# SCH_LED-bargraph-1_5_2024-10-24.net
KiCad netlist of a schematic drawn in EasyEDA
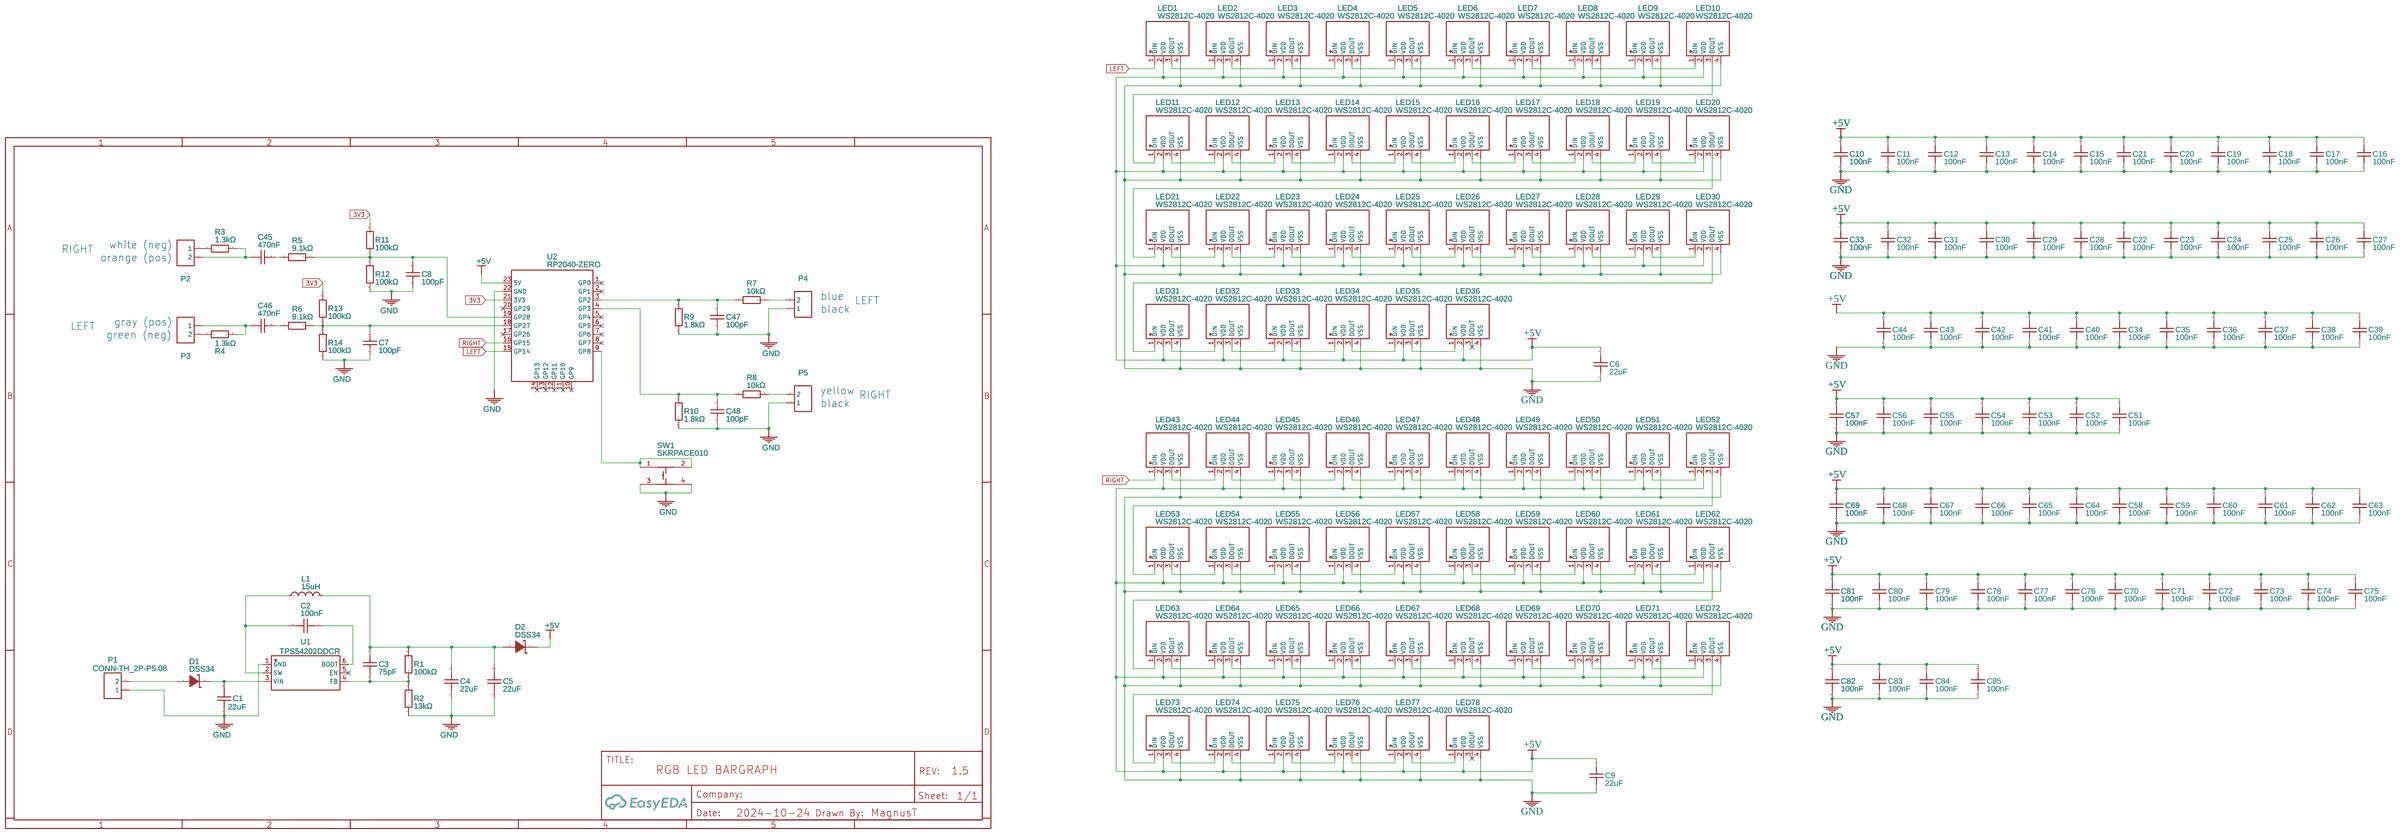
[diagram p0: schematic sheet]

(export (version "E")
  (design (tool "Eeschema 10.0.6"))
  (components
    (comp (ref "C1")
      (value "22uF")
      (fields
        (field (name "Manufacturer Part") "CL21A226MAYNNNE")
        (field (name "Manufacturer") "Samsung Electro-Mechanics")
      )
      (libsource (lib "") (part "CL21A226MAYNNNE"))
    )
    (comp (ref "C2")
      (value "100nF")
      (fields
        (field (name "Manufacturer Part") "CL05B104KO5NNNC")
        (field (name "Manufacturer") "SAMSUNG(三星)")
      )
      (libsource (lib "") (part "CL05B104KO5NNNC_1"))
    )
    (comp (ref "C3")
      (value "75pF")
      (fields
        (field (name "Manufacturer Part") "CC0603JRNPO9BN750")
        (field (name "Manufacturer") "YAGEO(国巨)")
      )
      (libsource (lib "") (part "CC0603JRNPO9BN750"))
    )
    (comp (ref "C4")
      (value "22uF")
      (fields (field (name "Manufacturer Part") "CL10A226MQ8NRNC") (field (name "Manufacturer") "SAMSUNG"))
      (libsource (lib "") (part "CL10A226MQ8NRNC"))
    )
    (comp (ref "C5")
      (value "22uF")
      (fields (field (name "Manufacturer Part") "CL10A226MQ8NRNC") (field (name "Manufacturer") "SAMSUNG"))
      (libsource (lib "") (part "CL10A226MQ8NRNC"))
    )
    (comp (ref "C6")
      (value "22uF")
      (fields (field (name "Manufacturer Part") "CL10A226MQ8NRNC") (field (name "Manufacturer") "SAMSUNG"))
      (libsource (lib "") (part "CL10A226MQ8NRNC"))
    )
    (comp (ref "C7")
      (value "100pF")
      (fields
        (field (name "Manufacturer Part") "CL10C101JB8NNNC")
        (field (name "Manufacturer") "SAMSUNG(三星)")
      )
      (libsource (lib "") (part "CL10C101JB8NNNC"))
    )
    (comp (ref "C8")
      (value "100pF")
      (fields
        (field (name "Manufacturer Part") "CL10C101JB8NNNC")
        (field (name "Manufacturer") "SAMSUNG(三星)")
      )
      (libsource (lib "") (part "CL10C101JB8NNNC"))
    )
    (comp (ref "C9")
      (value "22uF")
      (fields (field (name "Manufacturer Part") "CL10A226MQ8NRNC") (field (name "Manufacturer") "SAMSUNG"))
      (libsource (lib "") (part "CL10A226MQ8NRNC"))
    )
    (comp (ref "C10")
      (value "100nF")
      (fields
        (field (name "Manufacturer Part") "CL05B104KO5NNNC")
        (field (name "Manufacturer") "SAMSUNG(三星)")
      )
      (libsource (lib "") (part "CL05B104KO5NNNC"))
    )
    (comp (ref "C11")
      (value "100nF")
      (fields
        (field (name "Manufacturer Part") "CL05B104KO5NNNC")
        (field (name "Manufacturer") "SAMSUNG(三星)")
      )
      (libsource (lib "") (part "CL05B104KO5NNNC"))
    )
    (comp (ref "C12")
      (value "100nF")
      (fields
        (field (name "Manufacturer Part") "CL05B104KO5NNNC")
        (field (name "Manufacturer") "SAMSUNG(三星)")
      )
      (libsource (lib "") (part "CL05B104KO5NNNC"))
    )
    (comp (ref "C13")
      (value "100nF")
      (fields
        (field (name "Manufacturer Part") "CL05B104KO5NNNC")
        (field (name "Manufacturer") "SAMSUNG(三星)")
      )
      (libsource (lib "") (part "CL05B104KO5NNNC"))
    )
    (comp (ref "C14")
      (value "100nF")
      (fields
        (field (name "Manufacturer Part") "CL05B104KO5NNNC")
        (field (name "Manufacturer") "SAMSUNG(三星)")
      )
      (libsource (lib "") (part "CL05B104KO5NNNC"))
    )
    (comp (ref "C15")
      (value "100nF")
      (fields
        (field (name "Manufacturer Part") "CL05B104KO5NNNC")
        (field (name "Manufacturer") "SAMSUNG(三星)")
      )
      (libsource (lib "") (part "CL05B104KO5NNNC"))
    )
    (comp (ref "C16")
      (value "100nF")
      (fields
        (field (name "Manufacturer Part") "CL05B104KO5NNNC")
        (field (name "Manufacturer") "SAMSUNG(三星)")
      )
      (libsource (lib "") (part "CL05B104KO5NNNC"))
    )
    (comp (ref "C17")
      (value "100nF")
      (fields
        (field (name "Manufacturer Part") "CL05B104KO5NNNC")
        (field (name "Manufacturer") "SAMSUNG(三星)")
      )
      (libsource (lib "") (part "CL05B104KO5NNNC"))
    )
    (comp (ref "C18")
      (value "100nF")
      (fields
        (field (name "Manufacturer Part") "CL05B104KO5NNNC")
        (field (name "Manufacturer") "SAMSUNG(三星)")
      )
      (libsource (lib "") (part "CL05B104KO5NNNC"))
    )
    (comp (ref "C19")
      (value "100nF")
      (fields
        (field (name "Manufacturer Part") "CL05B104KO5NNNC")
        (field (name "Manufacturer") "SAMSUNG(三星)")
      )
      (libsource (lib "") (part "CL05B104KO5NNNC"))
    )
    (comp (ref "C20")
      (value "100nF")
      (fields
        (field (name "Manufacturer Part") "CL05B104KO5NNNC")
        (field (name "Manufacturer") "SAMSUNG(三星)")
      )
      (libsource (lib "") (part "CL05B104KO5NNNC"))
    )
    (comp (ref "C21")
      (value "100nF")
      (fields
        (field (name "Manufacturer Part") "CL05B104KO5NNNC")
        (field (name "Manufacturer") "SAMSUNG(三星)")
      )
      (libsource (lib "") (part "CL05B104KO5NNNC"))
    )
    (comp (ref "C22")
      (value "100nF")
      (fields
        (field (name "Manufacturer Part") "CL05B104KO5NNNC")
        (field (name "Manufacturer") "SAMSUNG(三星)")
      )
      (libsource (lib "") (part "CL05B104KO5NNNC"))
    )
    (comp (ref "C23")
      (value "100nF")
      (fields
        (field (name "Manufacturer Part") "CL05B104KO5NNNC")
        (field (name "Manufacturer") "SAMSUNG(三星)")
      )
      (libsource (lib "") (part "CL05B104KO5NNNC"))
    )
    (comp (ref "C24")
      (value "100nF")
      (fields
        (field (name "Manufacturer Part") "CL05B104KO5NNNC")
        (field (name "Manufacturer") "SAMSUNG(三星)")
      )
      (libsource (lib "") (part "CL05B104KO5NNNC"))
    )
    (comp (ref "C25")
      (value "100nF")
      (fields
        (field (name "Manufacturer Part") "CL05B104KO5NNNC")
        (field (name "Manufacturer") "SAMSUNG(三星)")
      )
      (libsource (lib "") (part "CL05B104KO5NNNC"))
    )
    (comp (ref "C26")
      (value "100nF")
      (fields
        (field (name "Manufacturer Part") "CL05B104KO5NNNC")
        (field (name "Manufacturer") "SAMSUNG(三星)")
      )
      (libsource (lib "") (part "CL05B104KO5NNNC"))
    )
    (comp (ref "C27")
      (value "100nF")
      (fields
        (field (name "Manufacturer Part") "CL05B104KO5NNNC")
        (field (name "Manufacturer") "SAMSUNG(三星)")
      )
      (libsource (lib "") (part "CL05B104KO5NNNC"))
    )
    (comp (ref "C28")
      (value "100nF")
      (fields
        (field (name "Manufacturer Part") "CL05B104KO5NNNC")
        (field (name "Manufacturer") "SAMSUNG(三星)")
      )
      (libsource (lib "") (part "CL05B104KO5NNNC"))
    )
    (comp (ref "C29")
      (value "100nF")
      (fields
        (field (name "Manufacturer Part") "CL05B104KO5NNNC")
        (field (name "Manufacturer") "SAMSUNG(三星)")
      )
      (libsource (lib "") (part "CL05B104KO5NNNC"))
    )
    (comp (ref "C30")
      (value "100nF")
      (fields
        (field (name "Manufacturer Part") "CL05B104KO5NNNC")
        (field (name "Manufacturer") "SAMSUNG(三星)")
      )
      (libsource (lib "") (part "CL05B104KO5NNNC"))
    )
    (comp (ref "C31")
      (value "100nF")
      (fields
        (field (name "Manufacturer Part") "CL05B104KO5NNNC")
        (field (name "Manufacturer") "SAMSUNG(三星)")
      )
      (libsource (lib "") (part "CL05B104KO5NNNC"))
    )
    (comp (ref "C32")
      (value "100nF")
      (fields
        (field (name "Manufacturer Part") "CL05B104KO5NNNC")
        (field (name "Manufacturer") "SAMSUNG(三星)")
      )
      (libsource (lib "") (part "CL05B104KO5NNNC"))
    )
    (comp (ref "C33")
      (value "100nF")
      (fields
        (field (name "Manufacturer Part") "CL05B104KO5NNNC")
        (field (name "Manufacturer") "SAMSUNG(三星)")
      )
      (libsource (lib "") (part "CL05B104KO5NNNC"))
    )
    (comp (ref "C34")
      (value "100nF")
      (fields
        (field (name "Manufacturer Part") "CL05B104KO5NNNC")
        (field (name "Manufacturer") "SAMSUNG(三星)")
      )
      (libsource (lib "") (part "CL05B104KO5NNNC"))
    )
    (comp (ref "C35")
      (value "100nF")
      (fields
        (field (name "Manufacturer Part") "CL05B104KO5NNNC")
        (field (name "Manufacturer") "SAMSUNG(三星)")
      )
      (libsource (lib "") (part "CL05B104KO5NNNC"))
    )
    (comp (ref "C36")
      (value "100nF")
      (fields
        (field (name "Manufacturer Part") "CL05B104KO5NNNC")
        (field (name "Manufacturer") "SAMSUNG(三星)")
      )
      (libsource (lib "") (part "CL05B104KO5NNNC"))
    )
    (comp (ref "C37")
      (value "100nF")
      (fields
        (field (name "Manufacturer Part") "CL05B104KO5NNNC")
        (field (name "Manufacturer") "SAMSUNG(三星)")
      )
      (libsource (lib "") (part "CL05B104KO5NNNC"))
    )
    (comp (ref "C38")
      (value "100nF")
      (fields
        (field (name "Manufacturer Part") "CL05B104KO5NNNC")
        (field (name "Manufacturer") "SAMSUNG(三星)")
      )
      (libsource (lib "") (part "CL05B104KO5NNNC"))
    )
    (comp (ref "C39")
      (value "100nF")
      (fields
        (field (name "Manufacturer Part") "CL05B104KO5NNNC")
        (field (name "Manufacturer") "SAMSUNG(三星)")
      )
      (libsource (lib "") (part "CL05B104KO5NNNC"))
    )
    (comp (ref "C40")
      (value "100nF")
      (fields
        (field (name "Manufacturer Part") "CL05B104KO5NNNC")
        (field (name "Manufacturer") "SAMSUNG(三星)")
      )
      (libsource (lib "") (part "CL05B104KO5NNNC"))
    )
    (comp (ref "C41")
      (value "100nF")
      (fields
        (field (name "Manufacturer Part") "CL05B104KO5NNNC")
        (field (name "Manufacturer") "SAMSUNG(三星)")
      )
      (libsource (lib "") (part "CL05B104KO5NNNC"))
    )
    (comp (ref "C42")
      (value "100nF")
      (fields
        (field (name "Manufacturer Part") "CL05B104KO5NNNC")
        (field (name "Manufacturer") "SAMSUNG(三星)")
      )
      (libsource (lib "") (part "CL05B104KO5NNNC"))
    )
    (comp (ref "C43")
      (value "100nF")
      (fields
        (field (name "Manufacturer Part") "CL05B104KO5NNNC")
        (field (name "Manufacturer") "SAMSUNG(三星)")
      )
      (libsource (lib "") (part "CL05B104KO5NNNC"))
    )
    (comp (ref "C44")
      (value "100nF")
      (fields
        (field (name "Manufacturer Part") "CL05B104KO5NNNC")
        (field (name "Manufacturer") "SAMSUNG(三星)")
      )
      (libsource (lib "") (part "CL05B104KO5NNNC"))
    )
    (comp (ref "C45")
      (value "470nF")
      (fields
        (field (name "Manufacturer Part") "CL21B474KBFNNNE")
        (field (name "Manufacturer") "SAMSUNG(三星)")
      )
      (libsource (lib "") (part "CL21B474KBFNNNE"))
    )
    (comp (ref "C46")
      (value "470nF")
      (fields
        (field (name "Manufacturer Part") "CL21B474KBFNNNE")
        (field (name "Manufacturer") "SAMSUNG(三星)")
      )
      (libsource (lib "") (part "CL21B474KBFNNNE"))
    )
    (comp (ref "C47")
      (value "100pF")
      (fields
        (field (name "Manufacturer Part") "CL10C101JB8NNNC")
        (field (name "Manufacturer") "SAMSUNG(三星)")
      )
      (libsource (lib "") (part "CL10C101JB8NNNC"))
    )
    (comp (ref "C48")
      (value "100pF")
      (fields
        (field (name "Manufacturer Part") "CL10C101JB8NNNC")
        (field (name "Manufacturer") "SAMSUNG(三星)")
      )
      (libsource (lib "") (part "CL10C101JB8NNNC"))
    )
    (comp (ref "C51")
      (value "100nF")
      (fields
        (field (name "Manufacturer Part") "CL05B104KO5NNNC")
        (field (name "Manufacturer") "SAMSUNG(三星)")
      )
      (libsource (lib "") (part "CL05B104KO5NNNC"))
    )
    (comp (ref "C52")
      (value "100nF")
      (fields
        (field (name "Manufacturer Part") "CL05B104KO5NNNC")
        (field (name "Manufacturer") "SAMSUNG(三星)")
      )
      (libsource (lib "") (part "CL05B104KO5NNNC"))
    )
    (comp (ref "C53")
      (value "100nF")
      (fields
        (field (name "Manufacturer Part") "CL05B104KO5NNNC")
        (field (name "Manufacturer") "SAMSUNG(三星)")
      )
      (libsource (lib "") (part "CL05B104KO5NNNC"))
    )
    (comp (ref "C54")
      (value "100nF")
      (fields
        (field (name "Manufacturer Part") "CL05B104KO5NNNC")
        (field (name "Manufacturer") "SAMSUNG(三星)")
      )
      (libsource (lib "") (part "CL05B104KO5NNNC"))
    )
    (comp (ref "C55")
      (value "100nF")
      (fields
        (field (name "Manufacturer Part") "CL05B104KO5NNNC")
        (field (name "Manufacturer") "SAMSUNG(三星)")
      )
      (libsource (lib "") (part "CL05B104KO5NNNC"))
    )
    (comp (ref "C56")
      (value "100nF")
      (fields
        (field (name "Manufacturer Part") "CL05B104KO5NNNC")
        (field (name "Manufacturer") "SAMSUNG(三星)")
      )
      (libsource (lib "") (part "CL05B104KO5NNNC"))
    )
    (comp (ref "C57")
      (value "100nF")
      (fields
        (field (name "Manufacturer Part") "CL05B104KO5NNNC")
        (field (name "Manufacturer") "SAMSUNG(三星)")
      )
      (libsource (lib "") (part "CL05B104KO5NNNC"))
    )
    (comp (ref "C58")
      (value "100nF")
      (fields
        (field (name "Manufacturer Part") "CL05B104KO5NNNC")
        (field (name "Manufacturer") "SAMSUNG(三星)")
      )
      (libsource (lib "") (part "CL05B104KO5NNNC"))
    )
    (comp (ref "C59")
      (value "100nF")
      (fields
        (field (name "Manufacturer Part") "CL05B104KO5NNNC")
        (field (name "Manufacturer") "SAMSUNG(三星)")
      )
      (libsource (lib "") (part "CL05B104KO5NNNC"))
    )
    (comp (ref "C60")
      (value "100nF")
      (fields
        (field (name "Manufacturer Part") "CL05B104KO5NNNC")
        (field (name "Manufacturer") "SAMSUNG(三星)")
      )
      (libsource (lib "") (part "CL05B104KO5NNNC"))
    )
    (comp (ref "C61")
      (value "100nF")
      (fields
        (field (name "Manufacturer Part") "CL05B104KO5NNNC")
        (field (name "Manufacturer") "SAMSUNG(三星)")
      )
      (libsource (lib "") (part "CL05B104KO5NNNC"))
    )
    (comp (ref "C62")
      (value "100nF")
      (fields
        (field (name "Manufacturer Part") "CL05B104KO5NNNC")
        (field (name "Manufacturer") "SAMSUNG(三星)")
      )
      (libsource (lib "") (part "CL05B104KO5NNNC"))
    )
    (comp (ref "C63")
      (value "100nF")
      (fields
        (field (name "Manufacturer Part") "CL05B104KO5NNNC")
        (field (name "Manufacturer") "SAMSUNG(三星)")
      )
      (libsource (lib "") (part "CL05B104KO5NNNC"))
    )
    (comp (ref "C64")
      (value "100nF")
      (fields
        (field (name "Manufacturer Part") "CL05B104KO5NNNC")
        (field (name "Manufacturer") "SAMSUNG(三星)")
      )
      (libsource (lib "") (part "CL05B104KO5NNNC"))
    )
    (comp (ref "C65")
      (value "100nF")
      (fields
        (field (name "Manufacturer Part") "CL05B104KO5NNNC")
        (field (name "Manufacturer") "SAMSUNG(三星)")
      )
      (libsource (lib "") (part "CL05B104KO5NNNC"))
    )
    (comp (ref "C66")
      (value "100nF")
      (fields
        (field (name "Manufacturer Part") "CL05B104KO5NNNC")
        (field (name "Manufacturer") "SAMSUNG(三星)")
      )
      (libsource (lib "") (part "CL05B104KO5NNNC"))
    )
    (comp (ref "C67")
      (value "100nF")
      (fields
        (field (name "Manufacturer Part") "CL05B104KO5NNNC")
        (field (name "Manufacturer") "SAMSUNG(三星)")
      )
      (libsource (lib "") (part "CL05B104KO5NNNC"))
    )
    (comp (ref "C68")
      (value "100nF")
      (fields
        (field (name "Manufacturer Part") "CL05B104KO5NNNC")
        (field (name "Manufacturer") "SAMSUNG(三星)")
      )
      (libsource (lib "") (part "CL05B104KO5NNNC"))
    )
    (comp (ref "C69")
      (value "100nF")
      (fields
        (field (name "Manufacturer Part") "CL05B104KO5NNNC")
        (field (name "Manufacturer") "SAMSUNG(三星)")
      )
      (libsource (lib "") (part "CL05B104KO5NNNC"))
    )
    (comp (ref "C70")
      (value "100nF")
      (fields
        (field (name "Manufacturer Part") "CL05B104KO5NNNC")
        (field (name "Manufacturer") "SAMSUNG(三星)")
      )
      (libsource (lib "") (part "CL05B104KO5NNNC"))
    )
    (comp (ref "C71")
      (value "100nF")
      (fields
        (field (name "Manufacturer Part") "CL05B104KO5NNNC")
        (field (name "Manufacturer") "SAMSUNG(三星)")
      )
      (libsource (lib "") (part "CL05B104KO5NNNC"))
    )
    (comp (ref "C72")
      (value "100nF")
      (fields
        (field (name "Manufacturer Part") "CL05B104KO5NNNC")
        (field (name "Manufacturer") "SAMSUNG(三星)")
      )
      (libsource (lib "") (part "CL05B104KO5NNNC"))
    )
    (comp (ref "C73")
      (value "100nF")
      (fields
        (field (name "Manufacturer Part") "CL05B104KO5NNNC")
        (field (name "Manufacturer") "SAMSUNG(三星)")
      )
      (libsource (lib "") (part "CL05B104KO5NNNC"))
    )
    (comp (ref "C74")
      (value "100nF")
      (fields
        (field (name "Manufacturer Part") "CL05B104KO5NNNC")
        (field (name "Manufacturer") "SAMSUNG(三星)")
      )
      (libsource (lib "") (part "CL05B104KO5NNNC"))
    )
    (comp (ref "C75")
      (value "100nF")
      (fields
        (field (name "Manufacturer Part") "CL05B104KO5NNNC")
        (field (name "Manufacturer") "SAMSUNG(三星)")
      )
      (libsource (lib "") (part "CL05B104KO5NNNC"))
    )
    (comp (ref "C76")
      (value "100nF")
      (fields
        (field (name "Manufacturer Part") "CL05B104KO5NNNC")
        (field (name "Manufacturer") "SAMSUNG(三星)")
      )
      (libsource (lib "") (part "CL05B104KO5NNNC"))
    )
    (comp (ref "C77")
      (value "100nF")
      (fields
        (field (name "Manufacturer Part") "CL05B104KO5NNNC")
        (field (name "Manufacturer") "SAMSUNG(三星)")
      )
      (libsource (lib "") (part "CL05B104KO5NNNC"))
    )
    (comp (ref "C78")
      (value "100nF")
      (fields
        (field (name "Manufacturer Part") "CL05B104KO5NNNC")
        (field (name "Manufacturer") "SAMSUNG(三星)")
      )
      (libsource (lib "") (part "CL05B104KO5NNNC"))
    )
    (comp (ref "C79")
      (value "100nF")
      (fields
        (field (name "Manufacturer Part") "CL05B104KO5NNNC")
        (field (name "Manufacturer") "SAMSUNG(三星)")
      )
      (libsource (lib "") (part "CL05B104KO5NNNC"))
    )
    (comp (ref "C80")
      (value "100nF")
      (fields
        (field (name "Manufacturer Part") "CL05B104KO5NNNC")
        (field (name "Manufacturer") "SAMSUNG(三星)")
      )
      (libsource (lib "") (part "CL05B104KO5NNNC"))
    )
    (comp (ref "C81")
      (value "100nF")
      (fields
        (field (name "Manufacturer Part") "CL05B104KO5NNNC")
        (field (name "Manufacturer") "SAMSUNG(三星)")
      )
      (libsource (lib "") (part "CL05B104KO5NNNC"))
    )
    (comp (ref "C82")
      (value "100nF")
      (fields
        (field (name "Manufacturer Part") "CL05B104KO5NNNC")
        (field (name "Manufacturer") "SAMSUNG(三星)")
      )
      (libsource (lib "") (part "CL05B104KO5NNNC"))
    )
    (comp (ref "C83")
      (value "100nF")
      (fields
        (field (name "Manufacturer Part") "CL05B104KO5NNNC")
        (field (name "Manufacturer") "SAMSUNG(三星)")
      )
      (libsource (lib "") (part "CL05B104KO5NNNC"))
    )
    (comp (ref "C84")
      (value "100nF")
      (fields
        (field (name "Manufacturer Part") "CL05B104KO5NNNC")
        (field (name "Manufacturer") "SAMSUNG(三星)")
      )
      (libsource (lib "") (part "CL05B104KO5NNNC"))
    )
    (comp (ref "C85")
      (value "100nF")
      (fields
        (field (name "Manufacturer Part") "CL05B104KO5NNNC")
        (field (name "Manufacturer") "SAMSUNG(三星)")
      )
      (libsource (lib "") (part "CL05B104KO5NNNC"))
    )
    (comp (ref "D1")
      (value "DSS34")
      (fields (field (name "Manufacturer") "STARSEA"))
      (libsource (lib "") (part "DSS34"))
    )
    (comp (ref "D2")
      (value "DSS34")
      (fields (field (name "Manufacturer") "STARSEA"))
      (libsource (lib "") (part "DSS34"))
    )
    (comp (ref "L1")
      (value "15uH")
      (fields
        (field (name "Manufacturer Part") "SLP6028S150MTT")
        (field (name "Manufacturer") "Sunltech(韩国顺磁)")
      )
      (libsource (lib "") (part "SLP6028S150MTT"))
    )
    (comp (ref "LED1")
      (value "WS2812C-4020")
      (fields (field (name "Manufacturer") "worldsemi"))
      (libsource (lib "") (part "WS2812C-4020"))
    )
    (comp (ref "LED2")
      (value "WS2812C-4020")
      (fields (field (name "Manufacturer") "worldsemi"))
      (libsource (lib "") (part "WS2812C-4020"))
    )
    (comp (ref "LED3")
      (value "WS2812C-4020")
      (fields (field (name "Manufacturer") "worldsemi"))
      (libsource (lib "") (part "WS2812C-4020"))
    )
    (comp (ref "LED4")
      (value "WS2812C-4020")
      (fields (field (name "Manufacturer") "worldsemi"))
      (libsource (lib "") (part "WS2812C-4020"))
    )
    (comp (ref "LED5")
      (value "WS2812C-4020")
      (fields (field (name "Manufacturer") "worldsemi"))
      (libsource (lib "") (part "WS2812C-4020"))
    )
    (comp (ref "LED6")
      (value "WS2812C-4020")
      (fields (field (name "Manufacturer") "worldsemi"))
      (libsource (lib "") (part "WS2812C-4020"))
    )
    (comp (ref "LED7")
      (value "WS2812C-4020")
      (fields (field (name "Manufacturer") "worldsemi"))
      (libsource (lib "") (part "WS2812C-4020"))
    )
    (comp (ref "LED8")
      (value "WS2812C-4020")
      (fields (field (name "Manufacturer") "worldsemi"))
      (libsource (lib "") (part "WS2812C-4020"))
    )
    (comp (ref "LED9")
      (value "WS2812C-4020")
      (fields (field (name "Manufacturer") "worldsemi"))
      (libsource (lib "") (part "WS2812C-4020"))
    )
    (comp (ref "LED10")
      (value "WS2812C-4020")
      (fields (field (name "Manufacturer") "worldsemi"))
      (libsource (lib "") (part "WS2812C-4020"))
    )
    (comp (ref "LED11")
      (value "WS2812C-4020")
      (fields (field (name "Manufacturer") "worldsemi"))
      (libsource (lib "") (part "WS2812C-4020"))
    )
    (comp (ref "LED12")
      (value "WS2812C-4020")
      (fields (field (name "Manufacturer") "worldsemi"))
      (libsource (lib "") (part "WS2812C-4020"))
    )
    (comp (ref "LED13")
      (value "WS2812C-4020")
      (fields (field (name "Manufacturer") "worldsemi"))
      (libsource (lib "") (part "WS2812C-4020"))
    )
    (comp (ref "LED14")
      (value "WS2812C-4020")
      (fields (field (name "Manufacturer") "worldsemi"))
      (libsource (lib "") (part "WS2812C-4020"))
    )
    (comp (ref "LED15")
      (value "WS2812C-4020")
      (fields (field (name "Manufacturer") "worldsemi"))
      (libsource (lib "") (part "WS2812C-4020"))
    )
    (comp (ref "LED16")
      (value "WS2812C-4020")
      (fields (field (name "Manufacturer") "worldsemi"))
      (libsource (lib "") (part "WS2812C-4020"))
    )
    (comp (ref "LED17")
      (value "WS2812C-4020")
      (fields (field (name "Manufacturer") "worldsemi"))
      (libsource (lib "") (part "WS2812C-4020"))
    )
    (comp (ref "LED18")
      (value "WS2812C-4020")
      (fields (field (name "Manufacturer") "worldsemi"))
      (libsource (lib "") (part "WS2812C-4020"))
    )
    (comp (ref "LED19")
      (value "WS2812C-4020")
      (fields (field (name "Manufacturer") "worldsemi"))
      (libsource (lib "") (part "WS2812C-4020"))
    )
    (comp (ref "LED20")
      (value "WS2812C-4020")
      (fields (field (name "Manufacturer") "worldsemi"))
      (libsource (lib "") (part "WS2812C-4020"))
    )
    (comp (ref "LED21")
      (value "WS2812C-4020")
      (fields (field (name "Manufacturer") "worldsemi"))
      (libsource (lib "") (part "WS2812C-4020"))
    )
    (comp (ref "LED22")
      (value "WS2812C-4020")
      (fields (field (name "Manufacturer") "worldsemi"))
      (libsource (lib "") (part "WS2812C-4020"))
    )
    (comp (ref "LED23")
      (value "WS2812C-4020")
      (fields (field (name "Manufacturer") "worldsemi"))
      (libsource (lib "") (part "WS2812C-4020"))
    )
    (comp (ref "LED24")
      (value "WS2812C-4020")
      (fields (field (name "Manufacturer") "worldsemi"))
      (libsource (lib "") (part "WS2812C-4020"))
    )
    (comp (ref "LED25")
      (value "WS2812C-4020")
      (fields (field (name "Manufacturer") "worldsemi"))
      (libsource (lib "") (part "WS2812C-4020"))
    )
    (comp (ref "LED26")
      (value "WS2812C-4020")
      (fields (field (name "Manufacturer") "worldsemi"))
      (libsource (lib "") (part "WS2812C-4020"))
    )
    (comp (ref "LED27")
      (value "WS2812C-4020")
      (fields (field (name "Manufacturer") "worldsemi"))
      (libsource (lib "") (part "WS2812C-4020"))
    )
    (comp (ref "LED28")
      (value "WS2812C-4020")
      (fields (field (name "Manufacturer") "worldsemi"))
      (libsource (lib "") (part "WS2812C-4020"))
    )
    (comp (ref "LED29")
      (value "WS2812C-4020")
      (fields (field (name "Manufacturer") "worldsemi"))
      (libsource (lib "") (part "WS2812C-4020"))
    )
    (comp (ref "LED30")
      (value "WS2812C-4020")
      (fields (field (name "Manufacturer") "worldsemi"))
      (libsource (lib "") (part "WS2812C-4020"))
    )
    (comp (ref "LED31")
      (value "WS2812C-4020")
      (fields (field (name "Manufacturer") "worldsemi"))
      (libsource (lib "") (part "WS2812C-4020"))
    )
    (comp (ref "LED32")
      (value "WS2812C-4020")
      (fields (field (name "Manufacturer") "worldsemi"))
      (libsource (lib "") (part "WS2812C-4020"))
    )
    (comp (ref "LED33")
      (value "WS2812C-4020")
      (fields (field (name "Manufacturer") "worldsemi"))
      (libsource (lib "") (part "WS2812C-4020"))
    )
    (comp (ref "LED34")
      (value "WS2812C-4020")
      (fields (field (name "Manufacturer") "worldsemi"))
      (libsource (lib "") (part "WS2812C-4020"))
    )
    (comp (ref "LED35")
      (value "WS2812C-4020")
      (fields (field (name "Manufacturer") "worldsemi"))
      (libsource (lib "") (part "WS2812C-4020"))
    )
    (comp (ref "LED36")
      (value "WS2812C-4020")
      (fields (field (name "Manufacturer") "worldsemi"))
      (libsource (lib "") (part "WS2812C-4020"))
    )
    (comp (ref "LED43")
      (value "WS2812C-4020")
      (fields (field (name "Manufacturer") "worldsemi"))
      (libsource (lib "") (part "WS2812C-4020"))
    )
    (comp (ref "LED44")
      (value "WS2812C-4020")
      (fields (field (name "Manufacturer") "worldsemi"))
      (libsource (lib "") (part "WS2812C-4020"))
    )
    (comp (ref "LED45")
      (value "WS2812C-4020")
      (fields (field (name "Manufacturer") "worldsemi"))
      (libsource (lib "") (part "WS2812C-4020"))
    )
    (comp (ref "LED46")
      (value "WS2812C-4020")
      (fields (field (name "Manufacturer") "worldsemi"))
      (libsource (lib "") (part "WS2812C-4020"))
    )
    (comp (ref "LED47")
      (value "WS2812C-4020")
      (fields (field (name "Manufacturer") "worldsemi"))
      (libsource (lib "") (part "WS2812C-4020"))
    )
    (comp (ref "LED48")
      (value "WS2812C-4020")
      (fields (field (name "Manufacturer") "worldsemi"))
      (libsource (lib "") (part "WS2812C-4020"))
    )
    (comp (ref "LED49")
      (value "WS2812C-4020")
      (fields (field (name "Manufacturer") "worldsemi"))
      (libsource (lib "") (part "WS2812C-4020"))
    )
    (comp (ref "LED50")
      (value "WS2812C-4020")
      (fields (field (name "Manufacturer") "worldsemi"))
      (libsource (lib "") (part "WS2812C-4020"))
    )
    (comp (ref "LED51")
      (value "WS2812C-4020")
      (fields (field (name "Manufacturer") "worldsemi"))
      (libsource (lib "") (part "WS2812C-4020"))
    )
    (comp (ref "LED52")
      (value "WS2812C-4020")
      (fields (field (name "Manufacturer") "worldsemi"))
      (libsource (lib "") (part "WS2812C-4020"))
    )
    (comp (ref "LED53")
      (value "WS2812C-4020")
      (fields (field (name "Manufacturer") "worldsemi"))
      (libsource (lib "") (part "WS2812C-4020"))
    )
    (comp (ref "LED54")
      (value "WS2812C-4020")
      (fields (field (name "Manufacturer") "worldsemi"))
      (libsource (lib "") (part "WS2812C-4020"))
    )
    (comp (ref "LED55")
      (value "WS2812C-4020")
      (fields (field (name "Manufacturer") "worldsemi"))
      (libsource (lib "") (part "WS2812C-4020"))
    )
    (comp (ref "LED56")
      (value "WS2812C-4020")
      (fields (field (name "Manufacturer") "worldsemi"))
      (libsource (lib "") (part "WS2812C-4020"))
    )
    (comp (ref "LED57")
      (value "WS2812C-4020")
      (fields (field (name "Manufacturer") "worldsemi"))
      (libsource (lib "") (part "WS2812C-4020"))
    )
    (comp (ref "LED58")
      (value "WS2812C-4020")
      (fields (field (name "Manufacturer") "worldsemi"))
      (libsource (lib "") (part "WS2812C-4020"))
    )
    (comp (ref "LED59")
      (value "WS2812C-4020")
      (fields (field (name "Manufacturer") "worldsemi"))
      (libsource (lib "") (part "WS2812C-4020"))
    )
    (comp (ref "LED60")
      (value "WS2812C-4020")
      (fields (field (name "Manufacturer") "worldsemi"))
      (libsource (lib "") (part "WS2812C-4020"))
    )
    (comp (ref "LED61")
      (value "WS2812C-4020")
      (fields (field (name "Manufacturer") "worldsemi"))
      (libsource (lib "") (part "WS2812C-4020"))
    )
    (comp (ref "LED62")
      (value "WS2812C-4020")
      (fields (field (name "Manufacturer") "worldsemi"))
      (libsource (lib "") (part "WS2812C-4020"))
    )
    (comp (ref "LED63")
      (value "WS2812C-4020")
      (fields (field (name "Manufacturer") "worldsemi"))
      (libsource (lib "") (part "WS2812C-4020"))
    )
    (comp (ref "LED64")
      (value "WS2812C-4020")
      (fields (field (name "Manufacturer") "worldsemi"))
      (libsource (lib "") (part "WS2812C-4020"))
    )
    (comp (ref "LED65")
      (value "WS2812C-4020")
      (fields (field (name "Manufacturer") "worldsemi"))
      (libsource (lib "") (part "WS2812C-4020"))
    )
    (comp (ref "LED66")
      (value "WS2812C-4020")
      (fields (field (name "Manufacturer") "worldsemi"))
      (libsource (lib "") (part "WS2812C-4020"))
    )
    (comp (ref "LED67")
      (value "WS2812C-4020")
      (fields (field (name "Manufacturer") "worldsemi"))
      (libsource (lib "") (part "WS2812C-4020"))
    )
    (comp (ref "LED68")
      (value "WS2812C-4020")
      (fields (field (name "Manufacturer") "worldsemi"))
      (libsource (lib "") (part "WS2812C-4020"))
    )
    (comp (ref "LED69")
      (value "WS2812C-4020")
      (fields (field (name "Manufacturer") "worldsemi"))
      (libsource (lib "") (part "WS2812C-4020"))
    )
    (comp (ref "LED70")
      (value "WS2812C-4020")
      (fields (field (name "Manufacturer") "worldsemi"))
      (libsource (lib "") (part "WS2812C-4020"))
    )
    (comp (ref "LED71")
      (value "WS2812C-4020")
      (fields (field (name "Manufacturer") "worldsemi"))
      (libsource (lib "") (part "WS2812C-4020"))
    )
    (comp (ref "LED72")
      (value "WS2812C-4020")
      (fields (field (name "Manufacturer") "worldsemi"))
      (libsource (lib "") (part "WS2812C-4020"))
    )
    (comp (ref "LED73")
      (value "WS2812C-4020")
      (fields (field (name "Manufacturer") "worldsemi"))
      (libsource (lib "") (part "WS2812C-4020"))
    )
    (comp (ref "LED74")
      (value "WS2812C-4020")
      (fields (field (name "Manufacturer") "worldsemi"))
      (libsource (lib "") (part "WS2812C-4020"))
    )
    (comp (ref "LED75")
      (value "WS2812C-4020")
      (fields (field (name "Manufacturer") "worldsemi"))
      (libsource (lib "") (part "WS2812C-4020"))
    )
    (comp (ref "LED76")
      (value "WS2812C-4020")
      (fields (field (name "Manufacturer") "worldsemi"))
      (libsource (lib "") (part "WS2812C-4020"))
    )
    (comp (ref "LED77")
      (value "WS2812C-4020")
      (fields (field (name "Manufacturer") "worldsemi"))
      (libsource (lib "") (part "WS2812C-4020"))
    )
    (comp (ref "LED78")
      (value "WS2812C-4020")
      (fields (field (name "Manufacturer") "worldsemi"))
      (libsource (lib "") (part "WS2812C-4020"))
    )
    (comp (ref "P1") (value "CONN-TH_2P-P5.08") (libsource (lib "") (part "CONN-TH_2P-P5.08_1")))
    (comp (ref "P2") (value "CONN-TH_2P-P5.08") (libsource (lib "") (part "CONN-TH_2P-P5.08")))
    (comp (ref "P3") (value "CONN-TH_2P-P5.08") (libsource (lib "") (part "CONN-TH_2P-P5.08")))
    (comp (ref "P4") (value "CONN-TH_2P-P5.08") (libsource (lib "") (part "CONN-TH_2P-P5.08_2")))
    (comp (ref "P5") (value "CONN-TH_2P-P5.08") (libsource (lib "") (part "CONN-TH_2P-P5.08_2")))
    (comp (ref "R1")
      (value "100kΩ")
      (fields
        (field (name "Manufacturer Part") "0603WAF1003T5E")
        (field (name "Manufacturer") "UNI-ROYAL(厚声)")
      )
      (libsource (lib "") (part "0603WAF1003T5E"))
    )
    (comp (ref "R2")
      (value "13kΩ")
      (fields
        (field (name "Manufacturer Part") "0603WAF1302T5E")
        (field (name "Manufacturer") "UNI-ROYAL(厚声)")
      )
      (libsource (lib "") (part "0603WAF1302T5E"))
    )
    (comp (ref "R3")
      (value "1.3kΩ")
      (fields
        (field (name "Manufacturer Part") "0603WAF1301T5E")
        (field (name "Manufacturer") "UNI-ROYAL(厚声)")
      )
      (libsource (lib "") (part "0603WAF1301T5E"))
    )
    (comp (ref "R4")
      (value "1.3kΩ")
      (fields
        (field (name "Manufacturer Part") "0603WAF1301T5E")
        (field (name "Manufacturer") "UNI-ROYAL(厚声)")
      )
      (libsource (lib "") (part "0603WAF1301T5E"))
    )
    (comp (ref "R5")
      (value "9.1kΩ")
      (fields
        (field (name "Manufacturer Part") "0603WAF9101T5E")
        (field (name "Manufacturer") "UNI-ROYAL(厚声)")
      )
      (libsource (lib "") (part "0603WAF9101T5E"))
    )
    (comp (ref "R6")
      (value "9.1kΩ")
      (fields
        (field (name "Manufacturer Part") "0603WAF9101T5E")
        (field (name "Manufacturer") "UNI-ROYAL(厚声)")
      )
      (libsource (lib "") (part "0603WAF9101T5E"))
    )
    (comp (ref "R7")
      (value "10kΩ")
      (fields
        (field (name "Manufacturer Part") "0603WAF1002T5E")
        (field (name "Manufacturer") "UNI-ROYAL(厚声)")
      )
      (libsource (lib "") (part "0603WAF1002T5E"))
    )
    (comp (ref "R8")
      (value "10kΩ")
      (fields
        (field (name "Manufacturer Part") "0603WAF1002T5E")
        (field (name "Manufacturer") "UNI-ROYAL(厚声)")
      )
      (libsource (lib "") (part "0603WAF1002T5E"))
    )
    (comp (ref "R9")
      (value "1.8kΩ")
      (fields
        (field (name "Manufacturer Part") "0603WAF1801T5E")
        (field (name "Manufacturer") "UNI-ROYAL(厚声)")
      )
      (libsource (lib "") (part "0603WAF1801T5E"))
    )
    (comp (ref "R10")
      (value "1.8kΩ")
      (fields
        (field (name "Manufacturer Part") "0603WAF1801T5E")
        (field (name "Manufacturer") "UNI-ROYAL(厚声)")
      )
      (libsource (lib "") (part "0603WAF1801T5E"))
    )
    (comp (ref "R11")
      (value "100kΩ")
      (fields
        (field (name "Manufacturer Part") "0603WAF1003T5E")
        (field (name "Manufacturer") "UNI-ROYAL(厚声)")
      )
      (libsource (lib "") (part "0603WAF1003T5E"))
    )
    (comp (ref "R12")
      (value "100kΩ")
      (fields
        (field (name "Manufacturer Part") "0603WAF1003T5E")
        (field (name "Manufacturer") "UNI-ROYAL(厚声)")
      )
      (libsource (lib "") (part "0603WAF1003T5E"))
    )
    (comp (ref "R13")
      (value "100kΩ")
      (fields
        (field (name "Manufacturer Part") "0603WAF1003T5E")
        (field (name "Manufacturer") "UNI-ROYAL(厚声)")
      )
      (libsource (lib "") (part "0603WAF1003T5E"))
    )
    (comp (ref "R14")
      (value "100kΩ")
      (fields
        (field (name "Manufacturer Part") "0603WAF1003T5E")
        (field (name "Manufacturer") "UNI-ROYAL(厚声)")
      )
      (libsource (lib "") (part "0603WAF1003T5E"))
    )
    (comp (ref "SW1")
      (value "SKRPACE010")
      (fields (field (name "Manufacturer") "ALPSALPINE(阿尔卑斯阿尔派)"))
      (libsource (lib "") (part "SKRPACE010"))
    )
    (comp (ref "U1")
      (value "TPS54202DDCR")
      (fields (field (name "Manufacturer") "TI(德州仪器)"))
      (libsource (lib "") (part "TPS54202DDCR"))
    )
    (comp (ref "U2")
      (value "RP2040-ZERO")
      (fields
        (field (name "Manufacturer Part") "RP2040-Zero")
        (field (name "Manufacturer") "Waveshare(微雪电子)")
      )
      (libsource (lib "") (part "RP2040-ZERO"))
    )
  )
  (nets
    (net (code "1") (name "+5V") (class "Default")
      (node (ref "C10") (pin "2") (pinfunction "2_2") (pintype "unspecified"))
      (node (ref "C11") (pin "2") (pinfunction "2_2") (pintype "unspecified"))
      (node (ref "C12") (pin "2") (pinfunction "2_2") (pintype "unspecified"))
      (node (ref "C13") (pin "2") (pinfunction "2_2") (pintype "unspecified"))
      (node (ref "C14") (pin "2") (pinfunction "2_2") (pintype "unspecified"))
      (node (ref "C15") (pin "2") (pinfunction "2_2") (pintype "unspecified"))
      (node (ref "C16") (pin "2") (pinfunction "2_2") (pintype "unspecified"))
      (node (ref "C17") (pin "2") (pinfunction "2_2") (pintype "unspecified"))
      (node (ref "C18") (pin "2") (pinfunction "2_2") (pintype "unspecified"))
      (node (ref "C19") (pin "2") (pinfunction "2_2") (pintype "unspecified"))
      (node (ref "C20") (pin "2") (pinfunction "2_2") (pintype "unspecified"))
      (node (ref "C21") (pin "2") (pinfunction "2_2") (pintype "unspecified"))
      (node (ref "C22") (pin "2") (pinfunction "2_2") (pintype "unspecified"))
      (node (ref "C23") (pin "2") (pinfunction "2_2") (pintype "unspecified"))
      (node (ref "C24") (pin "2") (pinfunction "2_2") (pintype "unspecified"))
      (node (ref "C25") (pin "2") (pinfunction "2_2") (pintype "unspecified"))
      (node (ref "C26") (pin "2") (pinfunction "2_2") (pintype "unspecified"))
      (node (ref "C27") (pin "2") (pinfunction "2_2") (pintype "unspecified"))
      (node (ref "C28") (pin "2") (pinfunction "2_2") (pintype "unspecified"))
      (node (ref "C29") (pin "2") (pinfunction "2_2") (pintype "unspecified"))
      (node (ref "C30") (pin "2") (pinfunction "2_2") (pintype "unspecified"))
      (node (ref "C31") (pin "2") (pinfunction "2_2") (pintype "unspecified"))
      (node (ref "C32") (pin "2") (pinfunction "2_2") (pintype "unspecified"))
      (node (ref "C33") (pin "2") (pinfunction "2_2") (pintype "unspecified"))
      (node (ref "C34") (pin "2") (pinfunction "2_2") (pintype "unspecified"))
      (node (ref "C35") (pin "2") (pinfunction "2_2") (pintype "unspecified"))
      (node (ref "C36") (pin "2") (pinfunction "2_2") (pintype "unspecified"))
      (node (ref "C37") (pin "2") (pinfunction "2_2") (pintype "unspecified"))
      (node (ref "C38") (pin "2") (pinfunction "2_2") (pintype "unspecified"))
      (node (ref "C39") (pin "2") (pinfunction "2_2") (pintype "unspecified"))
      (node (ref "C40") (pin "2") (pinfunction "2_2") (pintype "unspecified"))
      (node (ref "C41") (pin "2") (pinfunction "2_2") (pintype "unspecified"))
      (node (ref "C42") (pin "2") (pinfunction "2_2") (pintype "unspecified"))
      (node (ref "C43") (pin "2") (pinfunction "2_2") (pintype "unspecified"))
      (node (ref "C44") (pin "2") (pinfunction "2_2") (pintype "unspecified"))
      (node (ref "C51") (pin "2") (pinfunction "2_2") (pintype "unspecified"))
      (node (ref "C52") (pin "2") (pinfunction "2_2") (pintype "unspecified"))
      (node (ref "C53") (pin "2") (pinfunction "2_2") (pintype "unspecified"))
      (node (ref "C54") (pin "2") (pinfunction "2_2") (pintype "unspecified"))
      (node (ref "C55") (pin "2") (pinfunction "2_2") (pintype "unspecified"))
      (node (ref "C56") (pin "2") (pinfunction "2_2") (pintype "unspecified"))
      (node (ref "C57") (pin "2") (pinfunction "2_2") (pintype "unspecified"))
      (node (ref "C58") (pin "2") (pinfunction "2_2") (pintype "unspecified"))
      (node (ref "C59") (pin "2") (pinfunction "2_2") (pintype "unspecified"))
      (node (ref "C6") (pin "2") (pinfunction "2_2") (pintype "unspecified"))
      (node (ref "C60") (pin "2") (pinfunction "2_2") (pintype "unspecified"))
      (node (ref "C61") (pin "2") (pinfunction "2_2") (pintype "unspecified"))
      (node (ref "C62") (pin "2") (pinfunction "2_2") (pintype "unspecified"))
      (node (ref "C63") (pin "2") (pinfunction "2_2") (pintype "unspecified"))
      (node (ref "C64") (pin "2") (pinfunction "2_2") (pintype "unspecified"))
      (node (ref "C65") (pin "2") (pinfunction "2_2") (pintype "unspecified"))
      (node (ref "C66") (pin "2") (pinfunction "2_2") (pintype "unspecified"))
      (node (ref "C67") (pin "2") (pinfunction "2_2") (pintype "unspecified"))
      (node (ref "C68") (pin "2") (pinfunction "2_2") (pintype "unspecified"))
      (node (ref "C69") (pin "2") (pinfunction "2_2") (pintype "unspecified"))
      (node (ref "C70") (pin "2") (pinfunction "2_2") (pintype "unspecified"))
      (node (ref "C71") (pin "2") (pinfunction "2_2") (pintype "unspecified"))
      (node (ref "C72") (pin "2") (pinfunction "2_2") (pintype "unspecified"))
      (node (ref "C73") (pin "2") (pinfunction "2_2") (pintype "unspecified"))
      (node (ref "C74") (pin "2") (pinfunction "2_2") (pintype "unspecified"))
      (node (ref "C75") (pin "2") (pinfunction "2_2") (pintype "unspecified"))
      (node (ref "C76") (pin "2") (pinfunction "2_2") (pintype "unspecified"))
      (node (ref "C77") (pin "2") (pinfunction "2_2") (pintype "unspecified"))
      (node (ref "C78") (pin "2") (pinfunction "2_2") (pintype "unspecified"))
      (node (ref "C79") (pin "2") (pinfunction "2_2") (pintype "unspecified"))
      (node (ref "C80") (pin "2") (pinfunction "2_2") (pintype "unspecified"))
      (node (ref "C81") (pin "2") (pinfunction "2_2") (pintype "unspecified"))
      (node (ref "C82") (pin "2") (pinfunction "2_2") (pintype "unspecified"))
      (node (ref "C83") (pin "2") (pinfunction "2_2") (pintype "unspecified"))
      (node (ref "C84") (pin "2") (pinfunction "2_2") (pintype "unspecified"))
      (node (ref "C85") (pin "2") (pinfunction "2_2") (pintype "unspecified"))
      (node (ref "C9") (pin "2") (pinfunction "2_2") (pintype "unspecified"))
      (node (ref "D2") (pin "1") (pinfunction "K_1") (pintype "unspecified"))
      (node (ref "LED1") (pin "2") (pinfunction "VDD_2") (pintype "unspecified"))
      (node (ref "LED10") (pin "2") (pinfunction "VDD_2") (pintype "unspecified"))
      (node (ref "LED11") (pin "2") (pinfunction "VDD_2") (pintype "unspecified"))
      (node (ref "LED12") (pin "2") (pinfunction "VDD_2") (pintype "unspecified"))
      (node (ref "LED13") (pin "2") (pinfunction "VDD_2") (pintype "unspecified"))
      (node (ref "LED14") (pin "2") (pinfunction "VDD_2") (pintype "unspecified"))
      (node (ref "LED15") (pin "2") (pinfunction "VDD_2") (pintype "unspecified"))
      (node (ref "LED16") (pin "2") (pinfunction "VDD_2") (pintype "unspecified"))
      (node (ref "LED17") (pin "2") (pinfunction "VDD_2") (pintype "unspecified"))
      (node (ref "LED18") (pin "2") (pinfunction "VDD_2") (pintype "unspecified"))
      (node (ref "LED19") (pin "2") (pinfunction "VDD_2") (pintype "unspecified"))
      (node (ref "LED2") (pin "2") (pinfunction "VDD_2") (pintype "unspecified"))
      (node (ref "LED20") (pin "2") (pinfunction "VDD_2") (pintype "unspecified"))
      (node (ref "LED21") (pin "2") (pinfunction "VDD_2") (pintype "unspecified"))
      (node (ref "LED22") (pin "2") (pinfunction "VDD_2") (pintype "unspecified"))
      (node (ref "LED23") (pin "2") (pinfunction "VDD_2") (pintype "unspecified"))
      (node (ref "LED24") (pin "2") (pinfunction "VDD_2") (pintype "unspecified"))
      (node (ref "LED25") (pin "2") (pinfunction "VDD_2") (pintype "unspecified"))
      (node (ref "LED26") (pin "2") (pinfunction "VDD_2") (pintype "unspecified"))
      (node (ref "LED27") (pin "2") (pinfunction "VDD_2") (pintype "unspecified"))
      (node (ref "LED28") (pin "2") (pinfunction "VDD_2") (pintype "unspecified"))
      (node (ref "LED29") (pin "2") (pinfunction "VDD_2") (pintype "unspecified"))
      (node (ref "LED3") (pin "2") (pinfunction "VDD_2") (pintype "unspecified"))
      (node (ref "LED30") (pin "2") (pinfunction "VDD_2") (pintype "unspecified"))
      (node (ref "LED31") (pin "2") (pinfunction "VDD_2") (pintype "unspecified"))
      (node (ref "LED32") (pin "2") (pinfunction "VDD_2") (pintype "unspecified"))
      (node (ref "LED33") (pin "2") (pinfunction "VDD_2") (pintype "unspecified"))
      (node (ref "LED34") (pin "2") (pinfunction "VDD_2") (pintype "unspecified"))
      (node (ref "LED35") (pin "2") (pinfunction "VDD_2") (pintype "unspecified"))
      (node (ref "LED36") (pin "2") (pinfunction "VDD_2") (pintype "unspecified"))
      (node (ref "LED4") (pin "2") (pinfunction "VDD_2") (pintype "unspecified"))
      (node (ref "LED43") (pin "2") (pinfunction "VDD_2") (pintype "unspecified"))
      (node (ref "LED44") (pin "2") (pinfunction "VDD_2") (pintype "unspecified"))
      (node (ref "LED45") (pin "2") (pinfunction "VDD_2") (pintype "unspecified"))
      (node (ref "LED46") (pin "2") (pinfunction "VDD_2") (pintype "unspecified"))
      (node (ref "LED47") (pin "2") (pinfunction "VDD_2") (pintype "unspecified"))
      (node (ref "LED48") (pin "2") (pinfunction "VDD_2") (pintype "unspecified"))
      (node (ref "LED49") (pin "2") (pinfunction "VDD_2") (pintype "unspecified"))
      (node (ref "LED5") (pin "2") (pinfunction "VDD_2") (pintype "unspecified"))
      (node (ref "LED50") (pin "2") (pinfunction "VDD_2") (pintype "unspecified"))
      (node (ref "LED51") (pin "2") (pinfunction "VDD_2") (pintype "unspecified"))
      (node (ref "LED52") (pin "2") (pinfunction "VDD_2") (pintype "unspecified"))
      (node (ref "LED53") (pin "2") (pinfunction "VDD_2") (pintype "unspecified"))
      (node (ref "LED54") (pin "2") (pinfunction "VDD_2") (pintype "unspecified"))
      (node (ref "LED55") (pin "2") (pinfunction "VDD_2") (pintype "unspecified"))
      (node (ref "LED56") (pin "2") (pinfunction "VDD_2") (pintype "unspecified"))
      (node (ref "LED57") (pin "2") (pinfunction "VDD_2") (pintype "unspecified"))
      (node (ref "LED58") (pin "2") (pinfunction "VDD_2") (pintype "unspecified"))
      (node (ref "LED59") (pin "2") (pinfunction "VDD_2") (pintype "unspecified"))
      (node (ref "LED6") (pin "2") (pinfunction "VDD_2") (pintype "unspecified"))
      (node (ref "LED60") (pin "2") (pinfunction "VDD_2") (pintype "unspecified"))
      (node (ref "LED61") (pin "2") (pinfunction "VDD_2") (pintype "unspecified"))
      (node (ref "LED62") (pin "2") (pinfunction "VDD_2") (pintype "unspecified"))
      (node (ref "LED63") (pin "2") (pinfunction "VDD_2") (pintype "unspecified"))
      (node (ref "LED64") (pin "2") (pinfunction "VDD_2") (pintype "unspecified"))
      (node (ref "LED65") (pin "2") (pinfunction "VDD_2") (pintype "unspecified"))
      (node (ref "LED66") (pin "2") (pinfunction "VDD_2") (pintype "unspecified"))
      (node (ref "LED67") (pin "2") (pinfunction "VDD_2") (pintype "unspecified"))
      (node (ref "LED68") (pin "2") (pinfunction "VDD_2") (pintype "unspecified"))
      (node (ref "LED69") (pin "2") (pinfunction "VDD_2") (pintype "unspecified"))
      (node (ref "LED7") (pin "2") (pinfunction "VDD_2") (pintype "unspecified"))
      (node (ref "LED70") (pin "2") (pinfunction "VDD_2") (pintype "unspecified"))
      (node (ref "LED71") (pin "2") (pinfunction "VDD_2") (pintype "unspecified"))
      (node (ref "LED72") (pin "2") (pinfunction "VDD_2") (pintype "unspecified"))
      (node (ref "LED73") (pin "2") (pinfunction "VDD_2") (pintype "unspecified"))
      (node (ref "LED74") (pin "2") (pinfunction "VDD_2") (pintype "unspecified"))
      (node (ref "LED75") (pin "2") (pinfunction "VDD_2") (pintype "unspecified"))
      (node (ref "LED76") (pin "2") (pinfunction "VDD_2") (pintype "unspecified"))
      (node (ref "LED77") (pin "2") (pinfunction "VDD_2") (pintype "unspecified"))
      (node (ref "LED78") (pin "2") (pinfunction "VDD_2") (pintype "unspecified"))
      (node (ref "LED8") (pin "2") (pinfunction "VDD_2") (pintype "unspecified"))
      (node (ref "LED9") (pin "2") (pinfunction "VDD_2") (pintype "unspecified"))
      (node (ref "U2") (pin "23") (pinfunction "5V_23") (pintype "unspecified"))
    )
    (net (code "2") (name "3V3") (class "Default")
      (node (ref "R11") (pin "2") (pinfunction "2_2") (pintype "input"))
      (node (ref "R13") (pin "2") (pinfunction "2_2") (pintype "input"))
      (node (ref "U2") (pin "21") (pinfunction "3V3_21") (pintype "unspecified"))
    )
    (net (code "3") (name "GND") (class "Default")
      (node (ref "C1") (pin "1") (pinfunction "1_1") (pintype "unspecified"))
      (node (ref "C10") (pin "1") (pinfunction "1_1") (pintype "unspecified"))
      (node (ref "C11") (pin "1") (pinfunction "1_1") (pintype "unspecified"))
      (node (ref "C12") (pin "1") (pinfunction "1_1") (pintype "unspecified"))
      (node (ref "C13") (pin "1") (pinfunction "1_1") (pintype "unspecified"))
      (node (ref "C14") (pin "1") (pinfunction "1_1") (pintype "unspecified"))
      (node (ref "C15") (pin "1") (pinfunction "1_1") (pintype "unspecified"))
      (node (ref "C16") (pin "1") (pinfunction "1_1") (pintype "unspecified"))
      (node (ref "C17") (pin "1") (pinfunction "1_1") (pintype "unspecified"))
      (node (ref "C18") (pin "1") (pinfunction "1_1") (pintype "unspecified"))
      (node (ref "C19") (pin "1") (pinfunction "1_1") (pintype "unspecified"))
      (node (ref "C20") (pin "1") (pinfunction "1_1") (pintype "unspecified"))
      (node (ref "C21") (pin "1") (pinfunction "1_1") (pintype "unspecified"))
      (node (ref "C22") (pin "1") (pinfunction "1_1") (pintype "unspecified"))
      (node (ref "C23") (pin "1") (pinfunction "1_1") (pintype "unspecified"))
      (node (ref "C24") (pin "1") (pinfunction "1_1") (pintype "unspecified"))
      (node (ref "C25") (pin "1") (pinfunction "1_1") (pintype "unspecified"))
      (node (ref "C26") (pin "1") (pinfunction "1_1") (pintype "unspecified"))
      (node (ref "C27") (pin "1") (pinfunction "1_1") (pintype "unspecified"))
      (node (ref "C28") (pin "1") (pinfunction "1_1") (pintype "unspecified"))
      (node (ref "C29") (pin "1") (pinfunction "1_1") (pintype "unspecified"))
      (node (ref "C30") (pin "1") (pinfunction "1_1") (pintype "unspecified"))
      (node (ref "C31") (pin "1") (pinfunction "1_1") (pintype "unspecified"))
      (node (ref "C32") (pin "1") (pinfunction "1_1") (pintype "unspecified"))
      (node (ref "C33") (pin "1") (pinfunction "1_1") (pintype "unspecified"))
      (node (ref "C34") (pin "1") (pinfunction "1_1") (pintype "unspecified"))
      (node (ref "C35") (pin "1") (pinfunction "1_1") (pintype "unspecified"))
      (node (ref "C36") (pin "1") (pinfunction "1_1") (pintype "unspecified"))
      (node (ref "C37") (pin "1") (pinfunction "1_1") (pintype "unspecified"))
      (node (ref "C38") (pin "1") (pinfunction "1_1") (pintype "unspecified"))
      (node (ref "C39") (pin "1") (pinfunction "1_1") (pintype "unspecified"))
      (node (ref "C4") (pin "1") (pinfunction "1_1") (pintype "unspecified"))
      (node (ref "C40") (pin "1") (pinfunction "1_1") (pintype "unspecified"))
      (node (ref "C41") (pin "1") (pinfunction "1_1") (pintype "unspecified"))
      (node (ref "C42") (pin "1") (pinfunction "1_1") (pintype "unspecified"))
      (node (ref "C43") (pin "1") (pinfunction "1_1") (pintype "unspecified"))
      (node (ref "C44") (pin "1") (pinfunction "1_1") (pintype "unspecified"))
      (node (ref "C47") (pin "1") (pinfunction "1_1") (pintype "input"))
      (node (ref "C48") (pin "1") (pinfunction "1_1") (pintype "input"))
      (node (ref "C5") (pin "1") (pinfunction "1_1") (pintype "unspecified"))
      (node (ref "C51") (pin "1") (pinfunction "1_1") (pintype "unspecified"))
      (node (ref "C52") (pin "1") (pinfunction "1_1") (pintype "unspecified"))
      (node (ref "C53") (pin "1") (pinfunction "1_1") (pintype "unspecified"))
      (node (ref "C54") (pin "1") (pinfunction "1_1") (pintype "unspecified"))
      (node (ref "C55") (pin "1") (pinfunction "1_1") (pintype "unspecified"))
      (node (ref "C56") (pin "1") (pinfunction "1_1") (pintype "unspecified"))
      (node (ref "C57") (pin "1") (pinfunction "1_1") (pintype "unspecified"))
      (node (ref "C58") (pin "1") (pinfunction "1_1") (pintype "unspecified"))
      (node (ref "C59") (pin "1") (pinfunction "1_1") (pintype "unspecified"))
      (node (ref "C6") (pin "1") (pinfunction "1_1") (pintype "unspecified"))
      (node (ref "C60") (pin "1") (pinfunction "1_1") (pintype "unspecified"))
      (node (ref "C61") (pin "1") (pinfunction "1_1") (pintype "unspecified"))
      (node (ref "C62") (pin "1") (pinfunction "1_1") (pintype "unspecified"))
      (node (ref "C63") (pin "1") (pinfunction "1_1") (pintype "unspecified"))
      (node (ref "C64") (pin "1") (pinfunction "1_1") (pintype "unspecified"))
      (node (ref "C65") (pin "1") (pinfunction "1_1") (pintype "unspecified"))
      (node (ref "C66") (pin "1") (pinfunction "1_1") (pintype "unspecified"))
      (node (ref "C67") (pin "1") (pinfunction "1_1") (pintype "unspecified"))
      (node (ref "C68") (pin "1") (pinfunction "1_1") (pintype "unspecified"))
      (node (ref "C69") (pin "1") (pinfunction "1_1") (pintype "unspecified"))
      (node (ref "C7") (pin "1") (pinfunction "1_1") (pintype "input"))
      (node (ref "C70") (pin "1") (pinfunction "1_1") (pintype "unspecified"))
      (node (ref "C71") (pin "1") (pinfunction "1_1") (pintype "unspecified"))
      (node (ref "C72") (pin "1") (pinfunction "1_1") (pintype "unspecified"))
      (node (ref "C73") (pin "1") (pinfunction "1_1") (pintype "unspecified"))
      (node (ref "C74") (pin "1") (pinfunction "1_1") (pintype "unspecified"))
      (node (ref "C75") (pin "1") (pinfunction "1_1") (pintype "unspecified"))
      (node (ref "C76") (pin "1") (pinfunction "1_1") (pintype "unspecified"))
      (node (ref "C77") (pin "1") (pinfunction "1_1") (pintype "unspecified"))
      (node (ref "C78") (pin "1") (pinfunction "1_1") (pintype "unspecified"))
      (node (ref "C79") (pin "1") (pinfunction "1_1") (pintype "unspecified"))
      (node (ref "C8") (pin "1") (pinfunction "1_1") (pintype "input"))
      (node (ref "C80") (pin "1") (pinfunction "1_1") (pintype "unspecified"))
      (node (ref "C81") (pin "1") (pinfunction "1_1") (pintype "unspecified"))
      (node (ref "C82") (pin "1") (pinfunction "1_1") (pintype "unspecified"))
      (node (ref "C83") (pin "1") (pinfunction "1_1") (pintype "unspecified"))
      (node (ref "C84") (pin "1") (pinfunction "1_1") (pintype "unspecified"))
      (node (ref "C85") (pin "1") (pinfunction "1_1") (pintype "unspecified"))
      (node (ref "C9") (pin "1") (pinfunction "1_1") (pintype "unspecified"))
      (node (ref "LED1") (pin "4") (pinfunction "VSS_4") (pintype "unspecified"))
      (node (ref "LED10") (pin "4") (pinfunction "VSS_4") (pintype "unspecified"))
      (node (ref "LED11") (pin "4") (pinfunction "VSS_4") (pintype "unspecified"))
      (node (ref "LED12") (pin "4") (pinfunction "VSS_4") (pintype "unspecified"))
      (node (ref "LED13") (pin "4") (pinfunction "VSS_4") (pintype "unspecified"))
      (node (ref "LED14") (pin "4") (pinfunction "VSS_4") (pintype "unspecified"))
      (node (ref "LED15") (pin "4") (pinfunction "VSS_4") (pintype "unspecified"))
      (node (ref "LED16") (pin "4") (pinfunction "VSS_4") (pintype "unspecified"))
      (node (ref "LED17") (pin "4") (pinfunction "VSS_4") (pintype "unspecified"))
      (node (ref "LED18") (pin "4") (pinfunction "VSS_4") (pintype "unspecified"))
      (node (ref "LED19") (pin "4") (pinfunction "VSS_4") (pintype "unspecified"))
      (node (ref "LED2") (pin "4") (pinfunction "VSS_4") (pintype "unspecified"))
      (node (ref "LED20") (pin "4") (pinfunction "VSS_4") (pintype "unspecified"))
      (node (ref "LED21") (pin "4") (pinfunction "VSS_4") (pintype "unspecified"))
      (node (ref "LED22") (pin "4") (pinfunction "VSS_4") (pintype "unspecified"))
      (node (ref "LED23") (pin "4") (pinfunction "VSS_4") (pintype "unspecified"))
      (node (ref "LED24") (pin "4") (pinfunction "VSS_4") (pintype "unspecified"))
      (node (ref "LED25") (pin "4") (pinfunction "VSS_4") (pintype "unspecified"))
      (node (ref "LED26") (pin "4") (pinfunction "VSS_4") (pintype "unspecified"))
      (node (ref "LED27") (pin "4") (pinfunction "VSS_4") (pintype "unspecified"))
      (node (ref "LED28") (pin "4") (pinfunction "VSS_4") (pintype "unspecified"))
      (node (ref "LED29") (pin "4") (pinfunction "VSS_4") (pintype "unspecified"))
      (node (ref "LED3") (pin "4") (pinfunction "VSS_4") (pintype "unspecified"))
      (node (ref "LED30") (pin "4") (pinfunction "VSS_4") (pintype "unspecified"))
      (node (ref "LED31") (pin "4") (pinfunction "VSS_4") (pintype "unspecified"))
      (node (ref "LED32") (pin "4") (pinfunction "VSS_4") (pintype "unspecified"))
      (node (ref "LED33") (pin "4") (pinfunction "VSS_4") (pintype "unspecified"))
      (node (ref "LED34") (pin "4") (pinfunction "VSS_4") (pintype "unspecified"))
      (node (ref "LED35") (pin "4") (pinfunction "VSS_4") (pintype "unspecified"))
      (node (ref "LED36") (pin "4") (pinfunction "VSS_4") (pintype "unspecified"))
      (node (ref "LED4") (pin "4") (pinfunction "VSS_4") (pintype "unspecified"))
      (node (ref "LED43") (pin "4") (pinfunction "VSS_4") (pintype "unspecified"))
      (node (ref "LED44") (pin "4") (pinfunction "VSS_4") (pintype "unspecified"))
      (node (ref "LED45") (pin "4") (pinfunction "VSS_4") (pintype "unspecified"))
      (node (ref "LED46") (pin "4") (pinfunction "VSS_4") (pintype "unspecified"))
      (node (ref "LED47") (pin "4") (pinfunction "VSS_4") (pintype "unspecified"))
      (node (ref "LED48") (pin "4") (pinfunction "VSS_4") (pintype "unspecified"))
      (node (ref "LED49") (pin "4") (pinfunction "VSS_4") (pintype "unspecified"))
      (node (ref "LED5") (pin "4") (pinfunction "VSS_4") (pintype "unspecified"))
      (node (ref "LED50") (pin "4") (pinfunction "VSS_4") (pintype "unspecified"))
      (node (ref "LED51") (pin "4") (pinfunction "VSS_4") (pintype "unspecified"))
      (node (ref "LED52") (pin "4") (pinfunction "VSS_4") (pintype "unspecified"))
      (node (ref "LED53") (pin "4") (pinfunction "VSS_4") (pintype "unspecified"))
      (node (ref "LED54") (pin "4") (pinfunction "VSS_4") (pintype "unspecified"))
      (node (ref "LED55") (pin "4") (pinfunction "VSS_4") (pintype "unspecified"))
      (node (ref "LED56") (pin "4") (pinfunction "VSS_4") (pintype "unspecified"))
      (node (ref "LED57") (pin "4") (pinfunction "VSS_4") (pintype "unspecified"))
      (node (ref "LED58") (pin "4") (pinfunction "VSS_4") (pintype "unspecified"))
      (node (ref "LED59") (pin "4") (pinfunction "VSS_4") (pintype "unspecified"))
      (node (ref "LED6") (pin "4") (pinfunction "VSS_4") (pintype "unspecified"))
      (node (ref "LED60") (pin "4") (pinfunction "VSS_4") (pintype "unspecified"))
      (node (ref "LED61") (pin "4") (pinfunction "VSS_4") (pintype "unspecified"))
      (node (ref "LED62") (pin "4") (pinfunction "VSS_4") (pintype "unspecified"))
      (node (ref "LED63") (pin "4") (pinfunction "VSS_4") (pintype "unspecified"))
      (node (ref "LED64") (pin "4") (pinfunction "VSS_4") (pintype "unspecified"))
      (node (ref "LED65") (pin "4") (pinfunction "VSS_4") (pintype "unspecified"))
      (node (ref "LED66") (pin "4") (pinfunction "VSS_4") (pintype "unspecified"))
      (node (ref "LED67") (pin "4") (pinfunction "VSS_4") (pintype "unspecified"))
      (node (ref "LED68") (pin "4") (pinfunction "VSS_4") (pintype "unspecified"))
      (node (ref "LED69") (pin "4") (pinfunction "VSS_4") (pintype "unspecified"))
      (node (ref "LED7") (pin "4") (pinfunction "VSS_4") (pintype "unspecified"))
      (node (ref "LED70") (pin "4") (pinfunction "VSS_4") (pintype "unspecified"))
      (node (ref "LED71") (pin "4") (pinfunction "VSS_4") (pintype "unspecified"))
      (node (ref "LED72") (pin "4") (pinfunction "VSS_4") (pintype "unspecified"))
      (node (ref "LED73") (pin "4") (pinfunction "VSS_4") (pintype "unspecified"))
      (node (ref "LED74") (pin "4") (pinfunction "VSS_4") (pintype "unspecified"))
      (node (ref "LED75") (pin "4") (pinfunction "VSS_4") (pintype "unspecified"))
      (node (ref "LED76") (pin "4") (pinfunction "VSS_4") (pintype "unspecified"))
      (node (ref "LED77") (pin "4") (pinfunction "VSS_4") (pintype "unspecified"))
      (node (ref "LED78") (pin "4") (pinfunction "VSS_4") (pintype "unspecified"))
      (node (ref "LED8") (pin "4") (pinfunction "VSS_4") (pintype "unspecified"))
      (node (ref "LED9") (pin "4") (pinfunction "VSS_4") (pintype "unspecified"))
      (node (ref "P1") (pin "1") (pinfunction "1_1") (pintype "unspecified"))
      (node (ref "P4") (pin "1") (pinfunction "1_1") (pintype "unspecified"))
      (node (ref "P5") (pin "1") (pinfunction "1_1") (pintype "unspecified"))
      (node (ref "R10") (pin "1") (pinfunction "1_1") (pintype "input"))
      (node (ref "R12") (pin "1") (pinfunction "1_1") (pintype "input"))
      (node (ref "R14") (pin "1") (pinfunction "1_1") (pintype "input"))
      (node (ref "R2") (pin "1") (pinfunction "1_1") (pintype "input"))
      (node (ref "R9") (pin "1") (pinfunction "1_1") (pintype "input"))
      (node (ref "SW1") (pin "3") (pinfunction "3_3") (pintype "unspecified"))
      (node (ref "SW1") (pin "4") (pinfunction "4_4") (pintype "unspecified"))
      (node (ref "U1") (pin "1") (pinfunction "GND_1") (pintype "unspecified"))
      (node (ref "U2") (pin "22") (pinfunction "GND_22") (pintype "unspecified"))
    )
    (net (code "4") (name "LEFT") (class "Default")
      (node (ref "LED1") (pin "1") (pinfunction "DIN_1") (pintype "unspecified"))
      (node (ref "U2") (pin "15") (pinfunction "GP14_15") (pintype "unspecified"))
    )
    (net (code "5") (name "Net-(C45-Pad1)") (class "Default")
      (node (ref "C45") (pin "1") (pinfunction "1_1") (pintype "input"))
      (node (ref "P2") (pin "2") (pinfunction "2_2") (pintype "unspecified"))
      (node (ref "R3") (pin "2") (pinfunction "2_2") (pintype "input"))
    )
    (net (code "6") (name "Net-(C45-Pad2)") (class "Default")
      (node (ref "C45") (pin "2") (pinfunction "2_2") (pintype "input"))
      (node (ref "R5") (pin "1") (pinfunction "1_1") (pintype "input"))
    )
    (net (code "7") (name "Net-(C46-Pad1)") (class "Default")
      (node (ref "C46") (pin "1") (pinfunction "1_1") (pintype "input"))
      (node (ref "P3") (pin "1") (pinfunction "1_1") (pintype "unspecified"))
      (node (ref "R4") (pin "2") (pinfunction "2_2") (pintype "input"))
    )
    (net (code "8") (name "Net-(C46-Pad2)") (class "Default")
      (node (ref "C46") (pin "2") (pinfunction "2_2") (pintype "input"))
      (node (ref "R6") (pin "1") (pinfunction "1_1") (pintype "input"))
    )
    (net (code "9") (name "Net-(D1-A)") (class "Default")
      (node (ref "D1") (pin "2") (pinfunction "A_2") (pintype "unspecified"))
      (node (ref "P1") (pin "2") (pinfunction "2_2") (pintype "unspecified"))
    )
    (net (code "10") (name "Net-(D1-K)") (class "Default")
      (node (ref "C1") (pin "2") (pinfunction "2_2") (pintype "unspecified"))
      (node (ref "D1") (pin "1") (pinfunction "K_1") (pintype "unspecified"))
      (node (ref "U1") (pin "3") (pinfunction "VIN_3") (pintype "unspecified"))
    )
    (net (code "11") (name "Net-(D2-A)") (class "Default")
      (node (ref "C3") (pin "2") (pinfunction "2_2") (pintype "unspecified"))
      (node (ref "C4") (pin "2") (pinfunction "2_2") (pintype "unspecified"))
      (node (ref "C5") (pin "2") (pinfunction "2_2") (pintype "unspecified"))
      (node (ref "D2") (pin "2") (pinfunction "A_2") (pintype "unspecified"))
      (node (ref "L1") (pin "2") (pinfunction "2_2") (pintype "unspecified"))
      (node (ref "R1") (pin "2") (pinfunction "2_2") (pintype "input"))
    )
    (net (code "12") (name "Net-(LED1-DOUT)") (class "Default")
      (node (ref "LED1") (pin "3") (pinfunction "DOUT_3") (pintype "unspecified"))
      (node (ref "LED2") (pin "1") (pinfunction "DIN_1") (pintype "unspecified"))
    )
    (net (code "13") (name "Net-(LED2-DOUT)") (class "Default")
      (node (ref "LED2") (pin "3") (pinfunction "DOUT_3") (pintype "unspecified"))
      (node (ref "LED3") (pin "1") (pinfunction "DIN_1") (pintype "unspecified"))
    )
    (net (code "14") (name "Net-(LED3-DOUT)") (class "Default")
      (node (ref "LED3") (pin "3") (pinfunction "DOUT_3") (pintype "unspecified"))
      (node (ref "LED4") (pin "1") (pinfunction "DIN_1") (pintype "unspecified"))
    )
    (net (code "15") (name "Net-(LED4-DOUT)") (class "Default")
      (node (ref "LED4") (pin "3") (pinfunction "DOUT_3") (pintype "unspecified"))
      (node (ref "LED5") (pin "1") (pinfunction "DIN_1") (pintype "unspecified"))
    )
    (net (code "16") (name "Net-(LED5-DOUT)") (class "Default")
      (node (ref "LED5") (pin "3") (pinfunction "DOUT_3") (pintype "unspecified"))
      (node (ref "LED6") (pin "1") (pinfunction "DIN_1") (pintype "unspecified"))
    )
    (net (code "17") (name "Net-(LED6-DOUT)") (class "Default")
      (node (ref "LED6") (pin "3") (pinfunction "DOUT_3") (pintype "unspecified"))
      (node (ref "LED7") (pin "1") (pinfunction "DIN_1") (pintype "unspecified"))
    )
    (net (code "18") (name "Net-(LED7-DOUT)") (class "Default")
      (node (ref "LED7") (pin "3") (pinfunction "DOUT_3") (pintype "unspecified"))
      (node (ref "LED8") (pin "1") (pinfunction "DIN_1") (pintype "unspecified"))
    )
    (net (code "19") (name "Net-(LED8-DOUT)") (class "Default")
      (node (ref "LED8") (pin "3") (pinfunction "DOUT_3") (pintype "unspecified"))
      (node (ref "LED9") (pin "1") (pinfunction "DIN_1") (pintype "unspecified"))
    )
    (net (code "20") (name "Net-(LED10-DIN)") (class "Default")
      (node (ref "LED10") (pin "1") (pinfunction "DIN_1") (pintype "unspecified"))
      (node (ref "LED9") (pin "3") (pinfunction "DOUT_3") (pintype "unspecified"))
    )
    (net (code "21") (name "Net-(LED10-DOUT)") (class "Default")
      (node (ref "LED10") (pin "3") (pinfunction "DOUT_3") (pintype "unspecified"))
      (node (ref "LED11") (pin "1") (pinfunction "DIN_1") (pintype "unspecified"))
    )
    (net (code "22") (name "Net-(LED11-DOUT)") (class "Default")
      (node (ref "LED11") (pin "3") (pinfunction "DOUT_3") (pintype "unspecified"))
      (node (ref "LED12") (pin "1") (pinfunction "DIN_1") (pintype "unspecified"))
    )
    (net (code "23") (name "Net-(LED12-DOUT)") (class "Default")
      (node (ref "LED12") (pin "3") (pinfunction "DOUT_3") (pintype "unspecified"))
      (node (ref "LED13") (pin "1") (pinfunction "DIN_1") (pintype "unspecified"))
    )
    (net (code "24") (name "Net-(LED13-DOUT)") (class "Default")
      (node (ref "LED13") (pin "3") (pinfunction "DOUT_3") (pintype "unspecified"))
      (node (ref "LED14") (pin "1") (pinfunction "DIN_1") (pintype "unspecified"))
    )
    (net (code "25") (name "Net-(LED14-DOUT)") (class "Default")
      (node (ref "LED14") (pin "3") (pinfunction "DOUT_3") (pintype "unspecified"))
      (node (ref "LED15") (pin "1") (pinfunction "DIN_1") (pintype "unspecified"))
    )
    (net (code "26") (name "Net-(LED15-DOUT)") (class "Default")
      (node (ref "LED15") (pin "3") (pinfunction "DOUT_3") (pintype "unspecified"))
      (node (ref "LED16") (pin "1") (pinfunction "DIN_1") (pintype "unspecified"))
    )
    (net (code "27") (name "Net-(LED16-DOUT)") (class "Default")
      (node (ref "LED16") (pin "3") (pinfunction "DOUT_3") (pintype "unspecified"))
      (node (ref "LED17") (pin "1") (pinfunction "DIN_1") (pintype "unspecified"))
    )
    (net (code "28") (name "Net-(LED17-DOUT)") (class "Default")
      (node (ref "LED17") (pin "3") (pinfunction "DOUT_3") (pintype "unspecified"))
      (node (ref "LED18") (pin "1") (pinfunction "DIN_1") (pintype "unspecified"))
    )
    (net (code "29") (name "Net-(LED18-DOUT)") (class "Default")
      (node (ref "LED18") (pin "3") (pinfunction "DOUT_3") (pintype "unspecified"))
      (node (ref "LED19") (pin "1") (pinfunction "DIN_1") (pintype "unspecified"))
    )
    (net (code "30") (name "Net-(LED19-DOUT)") (class "Default")
      (node (ref "LED19") (pin "3") (pinfunction "DOUT_3") (pintype "unspecified"))
      (node (ref "LED20") (pin "1") (pinfunction "DIN_1") (pintype "unspecified"))
    )
    (net (code "31") (name "Net-(LED20-DOUT)") (class "Default")
      (node (ref "LED20") (pin "3") (pinfunction "DOUT_3") (pintype "unspecified"))
      (node (ref "LED21") (pin "1") (pinfunction "DIN_1") (pintype "unspecified"))
    )
    (net (code "32") (name "Net-(LED21-DOUT)") (class "Default")
      (node (ref "LED21") (pin "3") (pinfunction "DOUT_3") (pintype "unspecified"))
      (node (ref "LED22") (pin "1") (pinfunction "DIN_1") (pintype "unspecified"))
    )
    (net (code "33") (name "Net-(LED22-DOUT)") (class "Default")
      (node (ref "LED22") (pin "3") (pinfunction "DOUT_3") (pintype "unspecified"))
      (node (ref "LED23") (pin "1") (pinfunction "DIN_1") (pintype "unspecified"))
    )
    (net (code "34") (name "Net-(LED23-DOUT)") (class "Default")
      (node (ref "LED23") (pin "3") (pinfunction "DOUT_3") (pintype "unspecified"))
      (node (ref "LED24") (pin "1") (pinfunction "DIN_1") (pintype "unspecified"))
    )
    (net (code "35") (name "Net-(LED24-DOUT)") (class "Default")
      (node (ref "LED24") (pin "3") (pinfunction "DOUT_3") (pintype "unspecified"))
      (node (ref "LED25") (pin "1") (pinfunction "DIN_1") (pintype "unspecified"))
    )
    (net (code "36") (name "Net-(LED25-DOUT)") (class "Default")
      (node (ref "LED25") (pin "3") (pinfunction "DOUT_3") (pintype "unspecified"))
      (node (ref "LED26") (pin "1") (pinfunction "DIN_1") (pintype "unspecified"))
    )
    (net (code "37") (name "Net-(LED26-DOUT)") (class "Default")
      (node (ref "LED26") (pin "3") (pinfunction "DOUT_3") (pintype "unspecified"))
      (node (ref "LED27") (pin "1") (pinfunction "DIN_1") (pintype "unspecified"))
    )
    (net (code "38") (name "Net-(LED27-DOUT)") (class "Default")
      (node (ref "LED27") (pin "3") (pinfunction "DOUT_3") (pintype "unspecified"))
      (node (ref "LED28") (pin "1") (pinfunction "DIN_1") (pintype "unspecified"))
    )
    (net (code "39") (name "Net-(LED28-DOUT)") (class "Default")
      (node (ref "LED28") (pin "3") (pinfunction "DOUT_3") (pintype "unspecified"))
      (node (ref "LED29") (pin "1") (pinfunction "DIN_1") (pintype "unspecified"))
    )
    (net (code "40") (name "Net-(LED29-DOUT)") (class "Default")
      (node (ref "LED29") (pin "3") (pinfunction "DOUT_3") (pintype "unspecified"))
      (node (ref "LED30") (pin "1") (pinfunction "DIN_1") (pintype "unspecified"))
    )
    (net (code "41") (name "Net-(LED30-DOUT)") (class "Default")
      (node (ref "LED30") (pin "3") (pinfunction "DOUT_3") (pintype "unspecified"))
      (node (ref "LED31") (pin "1") (pinfunction "DIN_1") (pintype "unspecified"))
    )
    (net (code "42") (name "Net-(LED31-DOUT)") (class "Default")
      (node (ref "LED31") (pin "3") (pinfunction "DOUT_3") (pintype "unspecified"))
      (node (ref "LED32") (pin "1") (pinfunction "DIN_1") (pintype "unspecified"))
    )
    (net (code "43") (name "Net-(LED32-DOUT)") (class "Default")
      (node (ref "LED32") (pin "3") (pinfunction "DOUT_3") (pintype "unspecified"))
      (node (ref "LED33") (pin "1") (pinfunction "DIN_1") (pintype "unspecified"))
    )
    (net (code "44") (name "Net-(LED33-DOUT)") (class "Default")
      (node (ref "LED33") (pin "3") (pinfunction "DOUT_3") (pintype "unspecified"))
      (node (ref "LED34") (pin "1") (pinfunction "DIN_1") (pintype "unspecified"))
    )
    (net (code "45") (name "Net-(LED34-DOUT)") (class "Default")
      (node (ref "LED34") (pin "3") (pinfunction "DOUT_3") (pintype "unspecified"))
      (node (ref "LED35") (pin "1") (pinfunction "DIN_1") (pintype "unspecified"))
    )
    (net (code "46") (name "Net-(LED35-DOUT)") (class "Default")
      (node (ref "LED35") (pin "3") (pinfunction "DOUT_3") (pintype "unspecified"))
      (node (ref "LED36") (pin "1") (pinfunction "DIN_1") (pintype "unspecified"))
    )
    (net (code "47") (name "Net-(LED43-DOUT)") (class "Default")
      (node (ref "LED43") (pin "3") (pinfunction "DOUT_3") (pintype "unspecified"))
      (node (ref "LED44") (pin "1") (pinfunction "DIN_1") (pintype "unspecified"))
    )
    (net (code "48") (name "Net-(LED44-DOUT)") (class "Default")
      (node (ref "LED44") (pin "3") (pinfunction "DOUT_3") (pintype "unspecified"))
      (node (ref "LED45") (pin "1") (pinfunction "DIN_1") (pintype "unspecified"))
    )
    (net (code "49") (name "Net-(LED45-DOUT)") (class "Default")
      (node (ref "LED45") (pin "3") (pinfunction "DOUT_3") (pintype "unspecified"))
      (node (ref "LED46") (pin "1") (pinfunction "DIN_1") (pintype "unspecified"))
    )
    (net (code "50") (name "Net-(LED46-DOUT)") (class "Default")
      (node (ref "LED46") (pin "3") (pinfunction "DOUT_3") (pintype "unspecified"))
      (node (ref "LED47") (pin "1") (pinfunction "DIN_1") (pintype "unspecified"))
    )
    (net (code "51") (name "Net-(LED47-DOUT)") (class "Default")
      (node (ref "LED47") (pin "3") (pinfunction "DOUT_3") (pintype "unspecified"))
      (node (ref "LED48") (pin "1") (pinfunction "DIN_1") (pintype "unspecified"))
    )
    (net (code "52") (name "Net-(LED48-DOUT)") (class "Default")
      (node (ref "LED48") (pin "3") (pinfunction "DOUT_3") (pintype "unspecified"))
      (node (ref "LED49") (pin "1") (pinfunction "DIN_1") (pintype "unspecified"))
    )
    (net (code "53") (name "Net-(LED49-DOUT)") (class "Default")
      (node (ref "LED49") (pin "3") (pinfunction "DOUT_3") (pintype "unspecified"))
      (node (ref "LED50") (pin "1") (pinfunction "DIN_1") (pintype "unspecified"))
    )
    (net (code "54") (name "Net-(LED50-DOUT)") (class "Default")
      (node (ref "LED50") (pin "3") (pinfunction "DOUT_3") (pintype "unspecified"))
      (node (ref "LED51") (pin "1") (pinfunction "DIN_1") (pintype "unspecified"))
    )
    (net (code "55") (name "Net-(LED51-DOUT)") (class "Default")
      (node (ref "LED51") (pin "3") (pinfunction "DOUT_3") (pintype "unspecified"))
      (node (ref "LED52") (pin "1") (pinfunction "DIN_1") (pintype "unspecified"))
    )
    (net (code "56") (name "Net-(LED52-DOUT)") (class "Default")
      (node (ref "LED52") (pin "3") (pinfunction "DOUT_3") (pintype "unspecified"))
      (node (ref "LED53") (pin "1") (pinfunction "DIN_1") (pintype "unspecified"))
    )
    (net (code "57") (name "Net-(LED53-DOUT)") (class "Default")
      (node (ref "LED53") (pin "3") (pinfunction "DOUT_3") (pintype "unspecified"))
      (node (ref "LED54") (pin "1") (pinfunction "DIN_1") (pintype "unspecified"))
    )
    (net (code "58") (name "Net-(LED54-DOUT)") (class "Default")
      (node (ref "LED54") (pin "3") (pinfunction "DOUT_3") (pintype "unspecified"))
      (node (ref "LED55") (pin "1") (pinfunction "DIN_1") (pintype "unspecified"))
    )
    (net (code "59") (name "Net-(LED55-DOUT)") (class "Default")
      (node (ref "LED55") (pin "3") (pinfunction "DOUT_3") (pintype "unspecified"))
      (node (ref "LED56") (pin "1") (pinfunction "DIN_1") (pintype "unspecified"))
    )
    (net (code "60") (name "Net-(LED56-DOUT)") (class "Default")
      (node (ref "LED56") (pin "3") (pinfunction "DOUT_3") (pintype "unspecified"))
      (node (ref "LED57") (pin "1") (pinfunction "DIN_1") (pintype "unspecified"))
    )
    (net (code "61") (name "Net-(LED57-DOUT)") (class "Default")
      (node (ref "LED57") (pin "3") (pinfunction "DOUT_3") (pintype "unspecified"))
      (node (ref "LED58") (pin "1") (pinfunction "DIN_1") (pintype "unspecified"))
    )
    (net (code "62") (name "Net-(LED58-DOUT)") (class "Default")
      (node (ref "LED58") (pin "3") (pinfunction "DOUT_3") (pintype "unspecified"))
      (node (ref "LED59") (pin "1") (pinfunction "DIN_1") (pintype "unspecified"))
    )
    (net (code "63") (name "Net-(LED59-DOUT)") (class "Default")
      (node (ref "LED59") (pin "3") (pinfunction "DOUT_3") (pintype "unspecified"))
      (node (ref "LED60") (pin "1") (pinfunction "DIN_1") (pintype "unspecified"))
    )
    (net (code "64") (name "Net-(LED60-DOUT)") (class "Default")
      (node (ref "LED60") (pin "3") (pinfunction "DOUT_3") (pintype "unspecified"))
      (node (ref "LED61") (pin "1") (pinfunction "DIN_1") (pintype "unspecified"))
    )
    (net (code "65") (name "Net-(LED61-DOUT)") (class "Default")
      (node (ref "LED61") (pin "3") (pinfunction "DOUT_3") (pintype "unspecified"))
      (node (ref "LED62") (pin "1") (pinfunction "DIN_1") (pintype "unspecified"))
    )
    (net (code "66") (name "Net-(LED62-DOUT)") (class "Default")
      (node (ref "LED62") (pin "3") (pinfunction "DOUT_3") (pintype "unspecified"))
      (node (ref "LED63") (pin "1") (pinfunction "DIN_1") (pintype "unspecified"))
    )
    (net (code "67") (name "Net-(LED63-DOUT)") (class "Default")
      (node (ref "LED63") (pin "3") (pinfunction "DOUT_3") (pintype "unspecified"))
      (node (ref "LED64") (pin "1") (pinfunction "DIN_1") (pintype "unspecified"))
    )
    (net (code "68") (name "Net-(LED64-DOUT)") (class "Default")
      (node (ref "LED64") (pin "3") (pinfunction "DOUT_3") (pintype "unspecified"))
      (node (ref "LED65") (pin "1") (pinfunction "DIN_1") (pintype "unspecified"))
    )
    (net (code "69") (name "Net-(LED65-DOUT)") (class "Default")
      (node (ref "LED65") (pin "3") (pinfunction "DOUT_3") (pintype "unspecified"))
      (node (ref "LED66") (pin "1") (pinfunction "DIN_1") (pintype "unspecified"))
    )
    (net (code "70") (name "Net-(LED66-DOUT)") (class "Default")
      (node (ref "LED66") (pin "3") (pinfunction "DOUT_3") (pintype "unspecified"))
      (node (ref "LED67") (pin "1") (pinfunction "DIN_1") (pintype "unspecified"))
    )
    (net (code "71") (name "Net-(LED67-DOUT)") (class "Default")
      (node (ref "LED67") (pin "3") (pinfunction "DOUT_3") (pintype "unspecified"))
      (node (ref "LED68") (pin "1") (pinfunction "DIN_1") (pintype "unspecified"))
    )
    (net (code "72") (name "Net-(LED68-DOUT)") (class "Default")
      (node (ref "LED68") (pin "3") (pinfunction "DOUT_3") (pintype "unspecified"))
      (node (ref "LED69") (pin "1") (pinfunction "DIN_1") (pintype "unspecified"))
    )
    (net (code "73") (name "Net-(LED69-DOUT)") (class "Default")
      (node (ref "LED69") (pin "3") (pinfunction "DOUT_3") (pintype "unspecified"))
      (node (ref "LED70") (pin "1") (pinfunction "DIN_1") (pintype "unspecified"))
    )
    (net (code "74") (name "Net-(LED70-DOUT)") (class "Default")
      (node (ref "LED70") (pin "3") (pinfunction "DOUT_3") (pintype "unspecified"))
      (node (ref "LED71") (pin "1") (pinfunction "DIN_1") (pintype "unspecified"))
    )
    (net (code "75") (name "Net-(LED71-DOUT)") (class "Default")
      (node (ref "LED71") (pin "3") (pinfunction "DOUT_3") (pintype "unspecified"))
      (node (ref "LED72") (pin "1") (pinfunction "DIN_1") (pintype "unspecified"))
    )
    (net (code "76") (name "Net-(LED72-DOUT)") (class "Default")
      (node (ref "LED72") (pin "3") (pinfunction "DOUT_3") (pintype "unspecified"))
      (node (ref "LED73") (pin "1") (pinfunction "DIN_1") (pintype "unspecified"))
    )
    (net (code "77") (name "Net-(LED73-DOUT)") (class "Default")
      (node (ref "LED73") (pin "3") (pinfunction "DOUT_3") (pintype "unspecified"))
      (node (ref "LED74") (pin "1") (pinfunction "DIN_1") (pintype "unspecified"))
    )
    (net (code "78") (name "Net-(LED74-DOUT)") (class "Default")
      (node (ref "LED74") (pin "3") (pinfunction "DOUT_3") (pintype "unspecified"))
      (node (ref "LED75") (pin "1") (pinfunction "DIN_1") (pintype "unspecified"))
    )
    (net (code "79") (name "Net-(LED75-DOUT)") (class "Default")
      (node (ref "LED75") (pin "3") (pinfunction "DOUT_3") (pintype "unspecified"))
      (node (ref "LED76") (pin "1") (pinfunction "DIN_1") (pintype "unspecified"))
    )
    (net (code "80") (name "Net-(LED76-DOUT)") (class "Default")
      (node (ref "LED76") (pin "3") (pinfunction "DOUT_3") (pintype "unspecified"))
      (node (ref "LED77") (pin "1") (pinfunction "DIN_1") (pintype "unspecified"))
    )
    (net (code "81") (name "Net-(LED77-DOUT)") (class "Default")
      (node (ref "LED77") (pin "3") (pinfunction "DOUT_3") (pintype "unspecified"))
      (node (ref "LED78") (pin "1") (pinfunction "DIN_1") (pintype "unspecified"))
    )
    (net (code "82") (name "Net-(P2-Pad1)") (class "Default")
      (node (ref "P2") (pin "1") (pinfunction "1_1") (pintype "unspecified"))
      (node (ref "R3") (pin "1") (pinfunction "1_1") (pintype "input"))
    )
    (net (code "83") (name "Net-(P3-Pad2)") (class "Default")
      (node (ref "P3") (pin "2") (pinfunction "2_2") (pintype "unspecified"))
      (node (ref "R4") (pin "1") (pinfunction "1_1") (pintype "input"))
    )
    (net (code "84") (name "Net-(P4-Pad2)") (class "Default")
      (node (ref "P4") (pin "2") (pinfunction "2_2") (pintype "unspecified"))
      (node (ref "R7") (pin "2") (pinfunction "2_2") (pintype "input"))
    )
    (net (code "85") (name "Net-(P5-Pad2)") (class "Default")
      (node (ref "P5") (pin "2") (pinfunction "2_2") (pintype "unspecified"))
      (node (ref "R8") (pin "2") (pinfunction "2_2") (pintype "input"))
    )
    (net (code "86") (name "Net-(U1-BOOT)") (class "Default")
      (node (ref "C2") (pin "1") (pinfunction "1_1") (pintype "unspecified"))
      (node (ref "U1") (pin "6") (pinfunction "BOOT_6") (pintype "unspecified"))
    )
    (net (code "87") (name "Net-(U1-FB)") (class "Default")
      (node (ref "C3") (pin "1") (pinfunction "1_1") (pintype "unspecified"))
      (node (ref "R1") (pin "1") (pinfunction "1_1") (pintype "input"))
      (node (ref "R2") (pin "2") (pinfunction "2_2") (pintype "input"))
      (node (ref "U1") (pin "4") (pinfunction "FB_4") (pintype "unspecified"))
    )
    (net (code "88") (name "Net-(U1-SW)") (class "Default")
      (node (ref "C2") (pin "2") (pinfunction "2_2") (pintype "unspecified"))
      (node (ref "L1") (pin "1") (pinfunction "1_1") (pintype "unspecified"))
      (node (ref "U1") (pin "2") (pinfunction "SW_2") (pintype "unspecified"))
    )
    (net (code "89") (name "Net-(U2-GP2)") (class "Default")
      (node (ref "C47") (pin "2") (pinfunction "2_2") (pintype "input"))
      (node (ref "R7") (pin "1") (pinfunction "1_1") (pintype "input"))
      (node (ref "R9") (pin "2") (pinfunction "2_2") (pintype "input"))
      (node (ref "U2") (pin "3") (pinfunction "GP2_3") (pintype "unspecified"))
    )
    (net (code "90") (name "Net-(U2-GP3)") (class "Default")
      (node (ref "C48") (pin "2") (pinfunction "2_2") (pintype "input"))
      (node (ref "R10") (pin "2") (pinfunction "2_2") (pintype "input"))
      (node (ref "R8") (pin "1") (pinfunction "1_1") (pintype "input"))
      (node (ref "U2") (pin "4") (pinfunction "GP3_4") (pintype "unspecified"))
    )
    (net (code "91") (name "Net-(U2-GP8)") (class "Default")
      (node (ref "SW1") (pin "1") (pinfunction "1_1") (pintype "unspecified"))
      (node (ref "SW1") (pin "2") (pinfunction "2_2") (pintype "unspecified"))
      (node (ref "U2") (pin "9") (pinfunction "GP8_9") (pintype "unspecified"))
    )
    (net (code "92") (name "Net-(U2-GP27)") (class "Default")
      (node (ref "C7") (pin "2") (pinfunction "2_2") (pintype "input"))
      (node (ref "R13") (pin "1") (pinfunction "1_1") (pintype "input"))
      (node (ref "R14") (pin "2") (pinfunction "2_2") (pintype "input"))
      (node (ref "R6") (pin "2") (pinfunction "2_2") (pintype "input"))
      (node (ref "U2") (pin "18") (pinfunction "GP27_18") (pintype "unspecified"))
    )
    (net (code "93") (name "Net-(U2-GP28)") (class "Default")
      (node (ref "C8") (pin "2") (pinfunction "2_2") (pintype "input"))
      (node (ref "R11") (pin "1") (pinfunction "1_1") (pintype "input"))
      (node (ref "R12") (pin "2") (pinfunction "2_2") (pintype "input"))
      (node (ref "R5") (pin "2") (pinfunction "2_2") (pintype "input"))
      (node (ref "U2") (pin "19") (pinfunction "GP28_19") (pintype "unspecified"))
    )
    (net (code "94") (name "RIGHT") (class "Default")
      (node (ref "LED43") (pin "1") (pinfunction "DIN_1") (pintype "unspecified"))
      (node (ref "U2") (pin "16") (pinfunction "GP15_16") (pintype "unspecified"))
    )
    (net (code "95") (name "unconnected-(LED36-DOUT-Pad3)") (class "Default")
      (node (ref "LED36") (pin "3") (pinfunction "DOUT_3") (pintype "unspecified+no_connect"))
    )
    (net (code "96") (name "unconnected-(LED78-DOUT-Pad3)") (class "Default")
      (node (ref "LED78") (pin "3") (pinfunction "DOUT_3") (pintype "unspecified+no_connect"))
    )
    (net (code "97") (name "unconnected-(U1-EN-Pad5)") (class "Default")
      (node (ref "U1") (pin "5") (pinfunction "EN_5") (pintype "unspecified+no_connect"))
    )
    (net (code "98") (name "unconnected-(U2-GP0-Pad1)") (class "Default")
      (node (ref "U2") (pin "1") (pinfunction "GP0_1") (pintype "unspecified+no_connect"))
    )
    (net (code "99") (name "unconnected-(U2-GP1-Pad2)") (class "Default")
      (node (ref "U2") (pin "2") (pinfunction "GP1_2") (pintype "unspecified+no_connect"))
    )
    (net (code "100") (name "unconnected-(U2-GP4-Pad5)") (class "Default")
      (node (ref "U2") (pin "5") (pinfunction "GP4_5") (pintype "unspecified+no_connect"))
    )
    (net (code "101") (name "unconnected-(U2-GP5-Pad6)") (class "Default")
      (node (ref "U2") (pin "6") (pinfunction "GP5_6") (pintype "unspecified+no_connect"))
    )
    (net (code "102") (name "unconnected-(U2-GP6-Pad7)") (class "Default")
      (node (ref "U2") (pin "7") (pinfunction "GP6_7") (pintype "unspecified+no_connect"))
    )
    (net (code "103") (name "unconnected-(U2-GP7-Pad8)") (class "Default")
      (node (ref "U2") (pin "8") (pinfunction "GP7_8") (pintype "unspecified+no_connect"))
    )
    (net (code "104") (name "unconnected-(U2-GP9-Pad10)") (class "Default")
      (node (ref "U2") (pin "10") (pinfunction "GP9_10") (pintype "unspecified+no_connect"))
    )
    (net (code "105") (name "unconnected-(U2-GP10-Pad11)") (class "Default")
      (node (ref "U2") (pin "11") (pinfunction "GP10_11") (pintype "unspecified+no_connect"))
    )
    (net (code "106") (name "unconnected-(U2-GP11-Pad12)") (class "Default")
      (node (ref "U2") (pin "12") (pinfunction "GP11_12") (pintype "unspecified+no_connect"))
    )
    (net (code "107") (name "unconnected-(U2-GP12-Pad13)") (class "Default")
      (node (ref "U2") (pin "13") (pinfunction "GP12_13") (pintype "unspecified+no_connect"))
    )
    (net (code "108") (name "unconnected-(U2-GP13-Pad14)") (class "Default")
      (node (ref "U2") (pin "14") (pinfunction "GP13_14") (pintype "unspecified+no_connect"))
    )
    (net (code "109") (name "unconnected-(U2-GP26-Pad17)") (class "Default")
      (node (ref "U2") (pin "17") (pinfunction "GP26_17") (pintype "unspecified+no_connect"))
    )
    (net (code "110") (name "unconnected-(U2-GP29-Pad20)") (class "Default")
      (node (ref "U2") (pin "20") (pinfunction "GP29_20") (pintype "unspecified+no_connect"))
    )
  )
)
